# MotherboardRev1.net
KiCad netlist of a schematic drawn in EAGLE
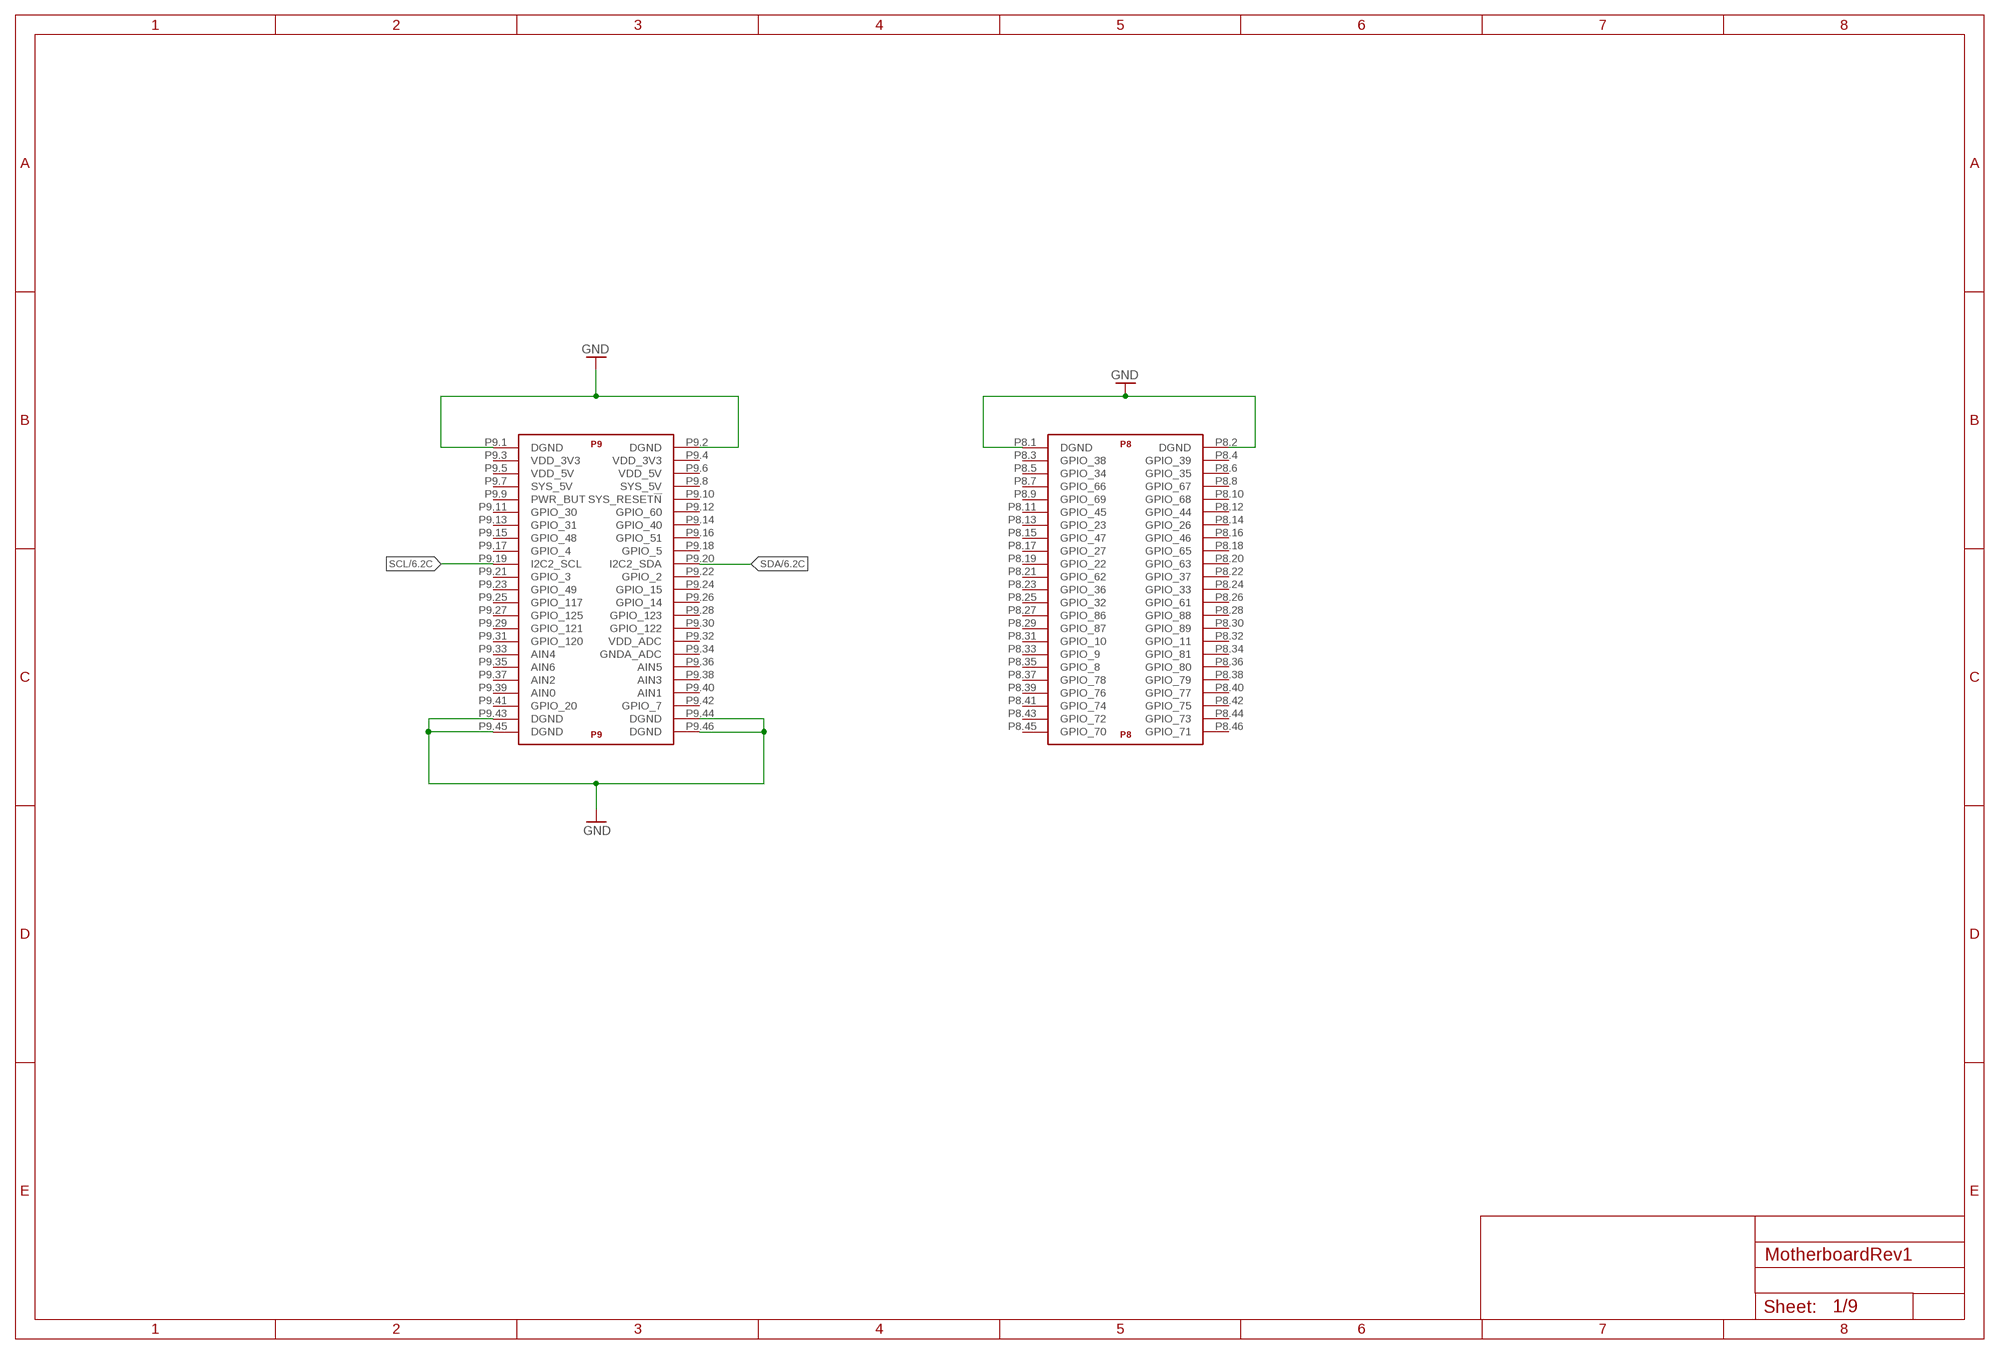
[diagram p0: schematic, sheet 1]
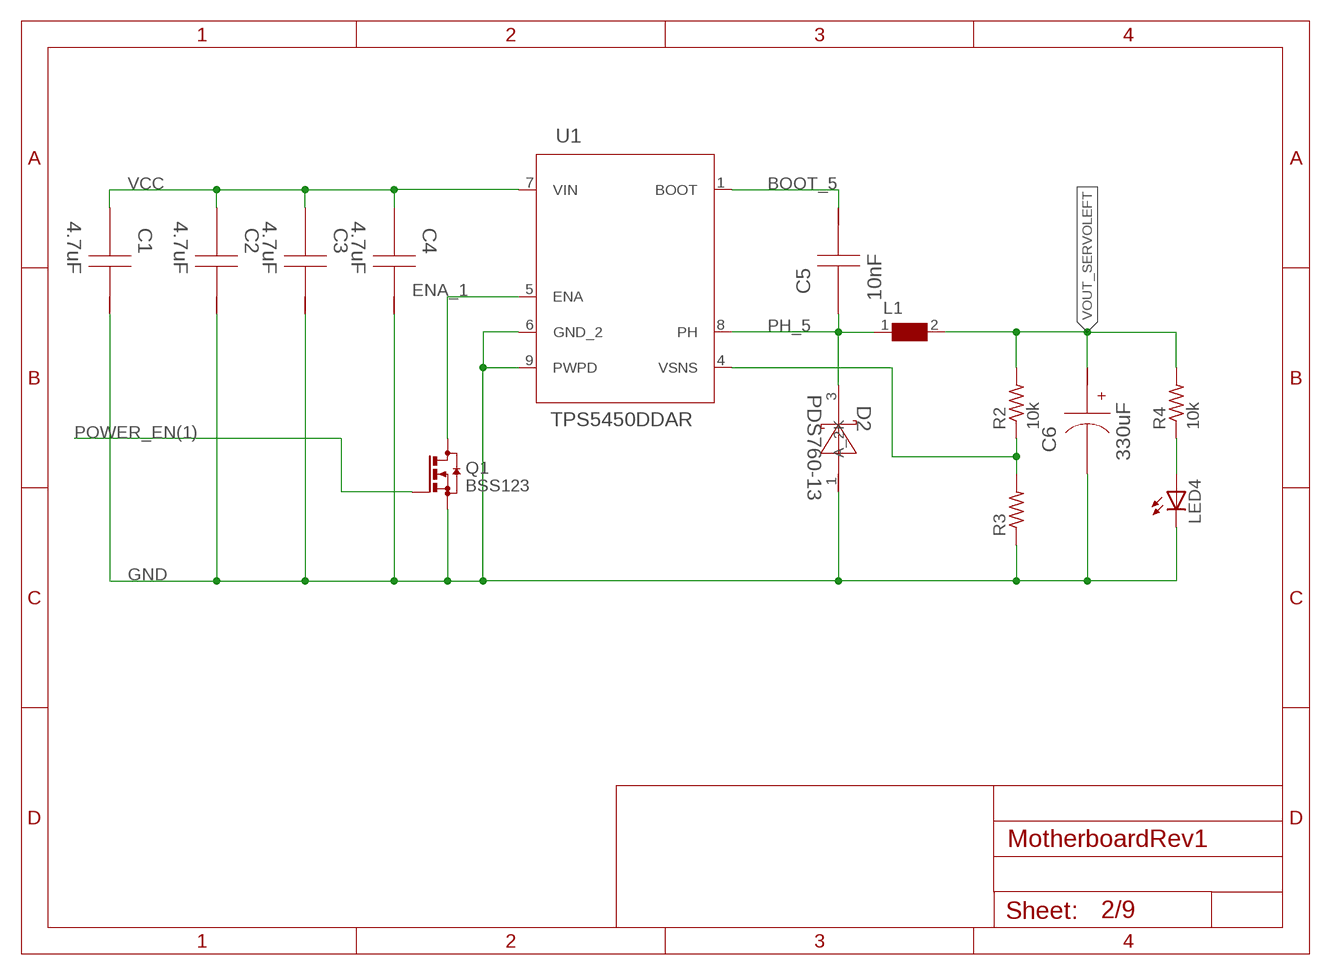
[diagram p1: schematic, sheet 2]
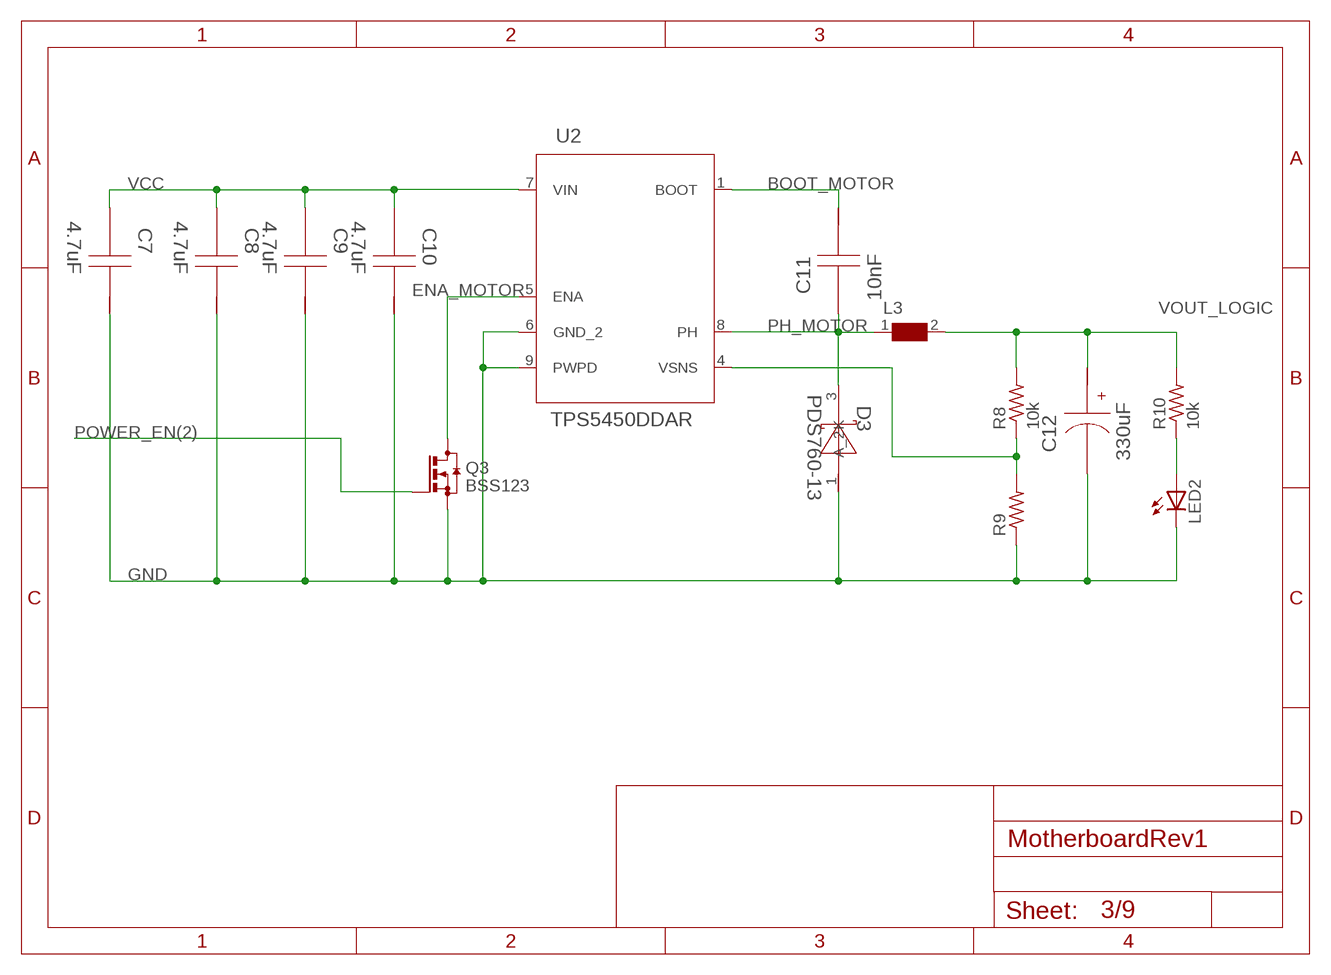
[diagram p2: schematic, sheet 3]
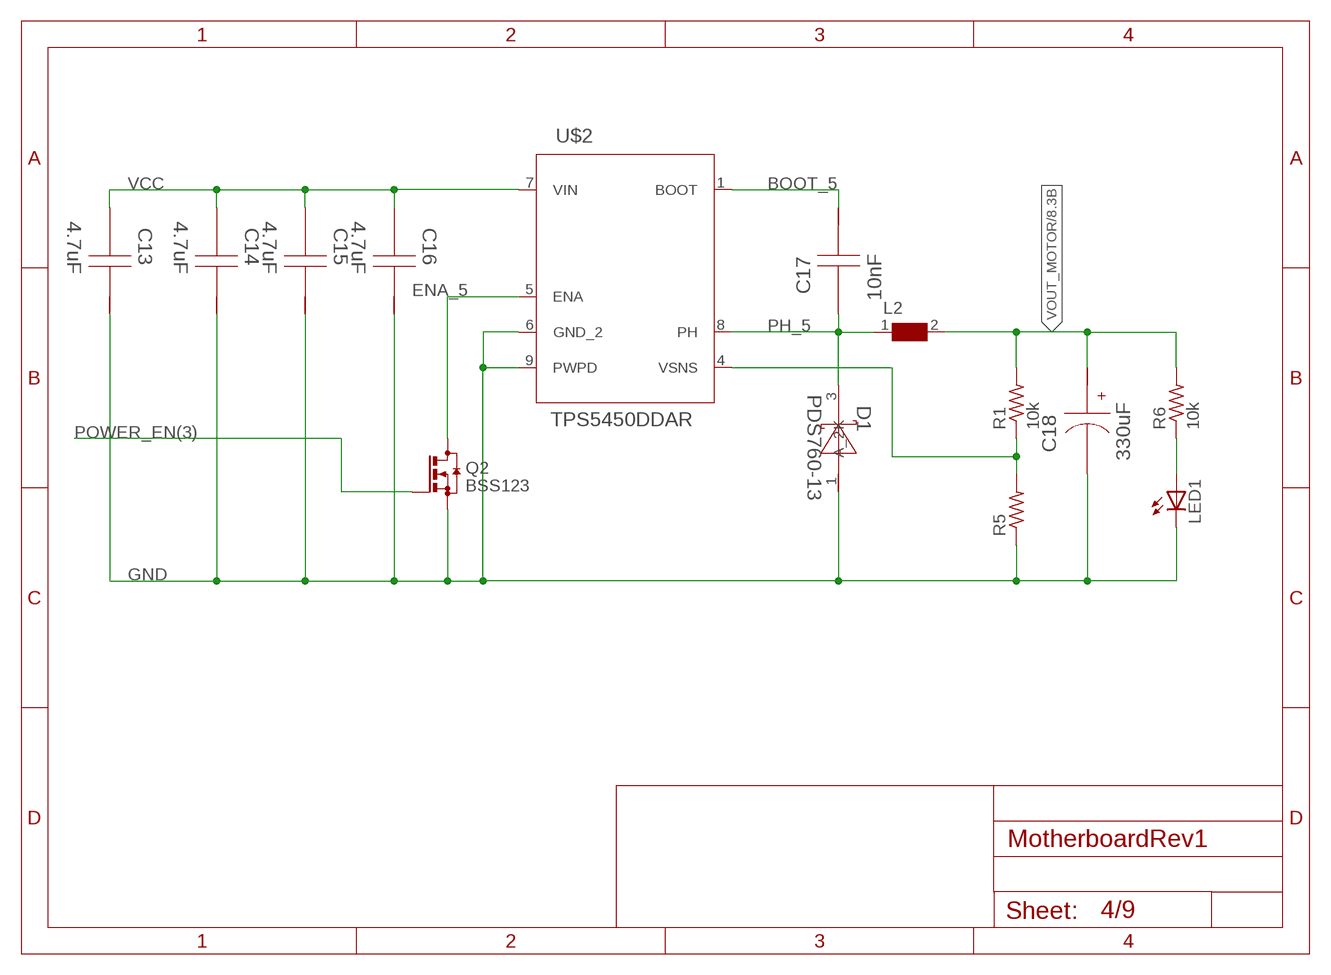
[diagram p3: schematic, sheet 4]
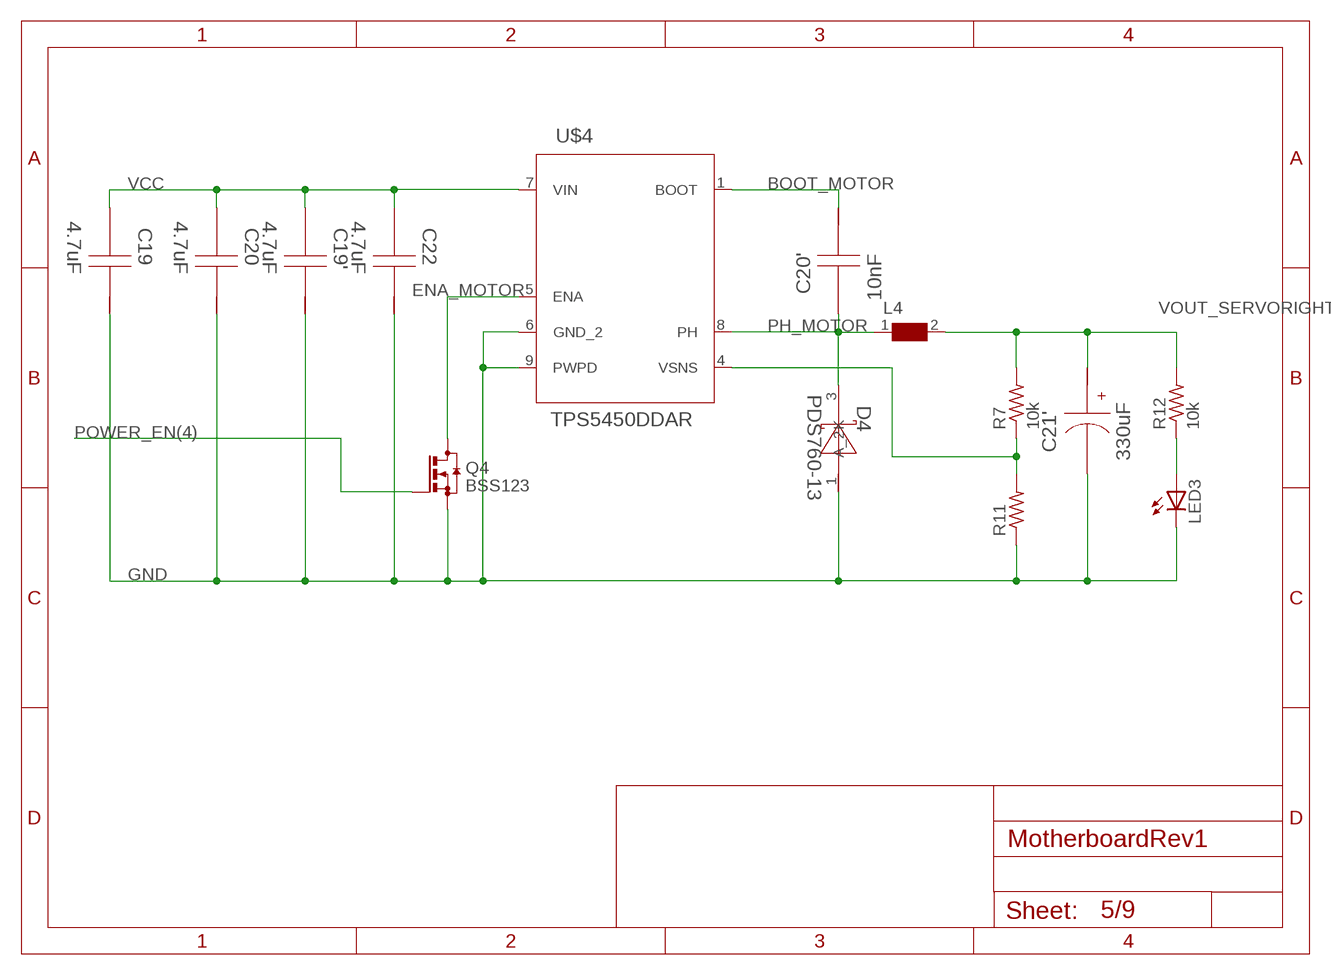
[diagram p4: schematic, sheet 5]
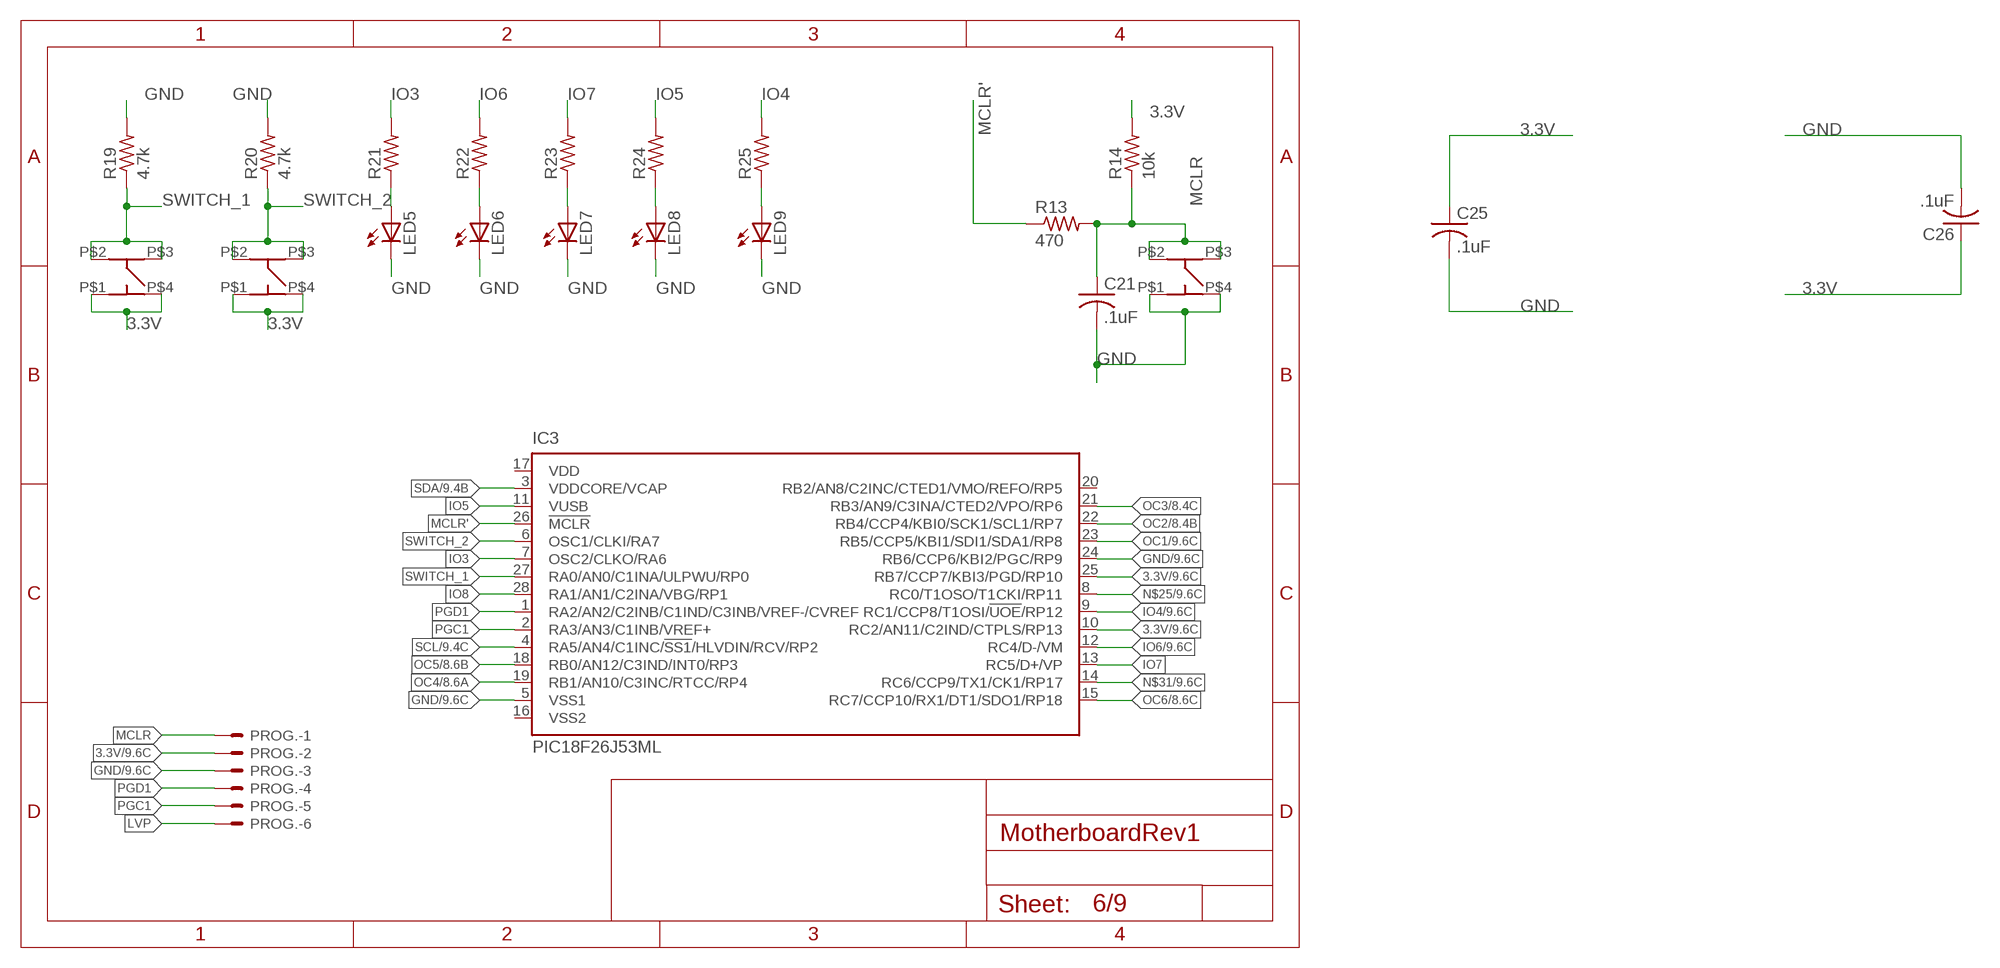
[diagram p5: schematic, sheet 6]
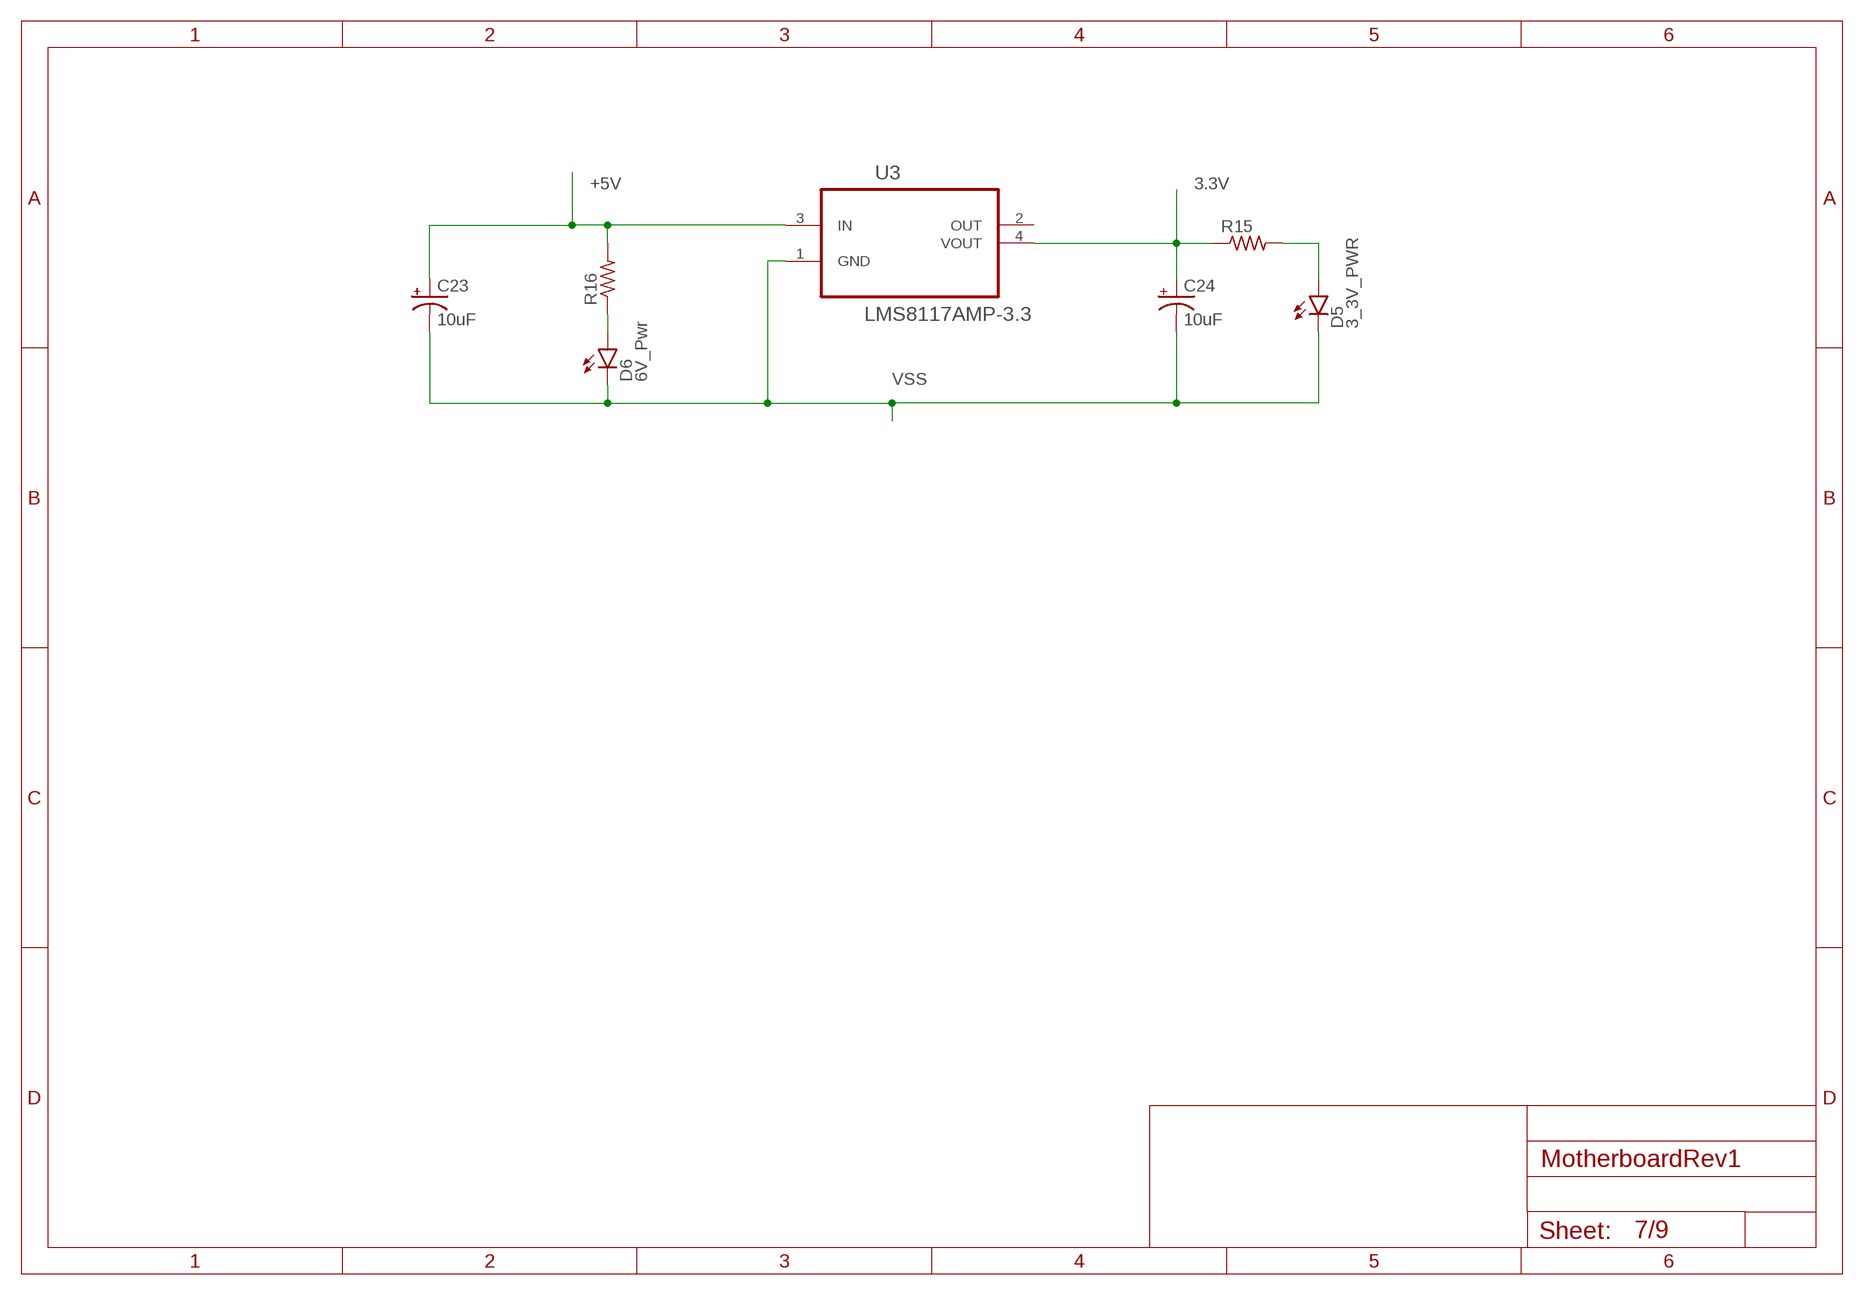
[diagram p6: schematic, sheet 7]
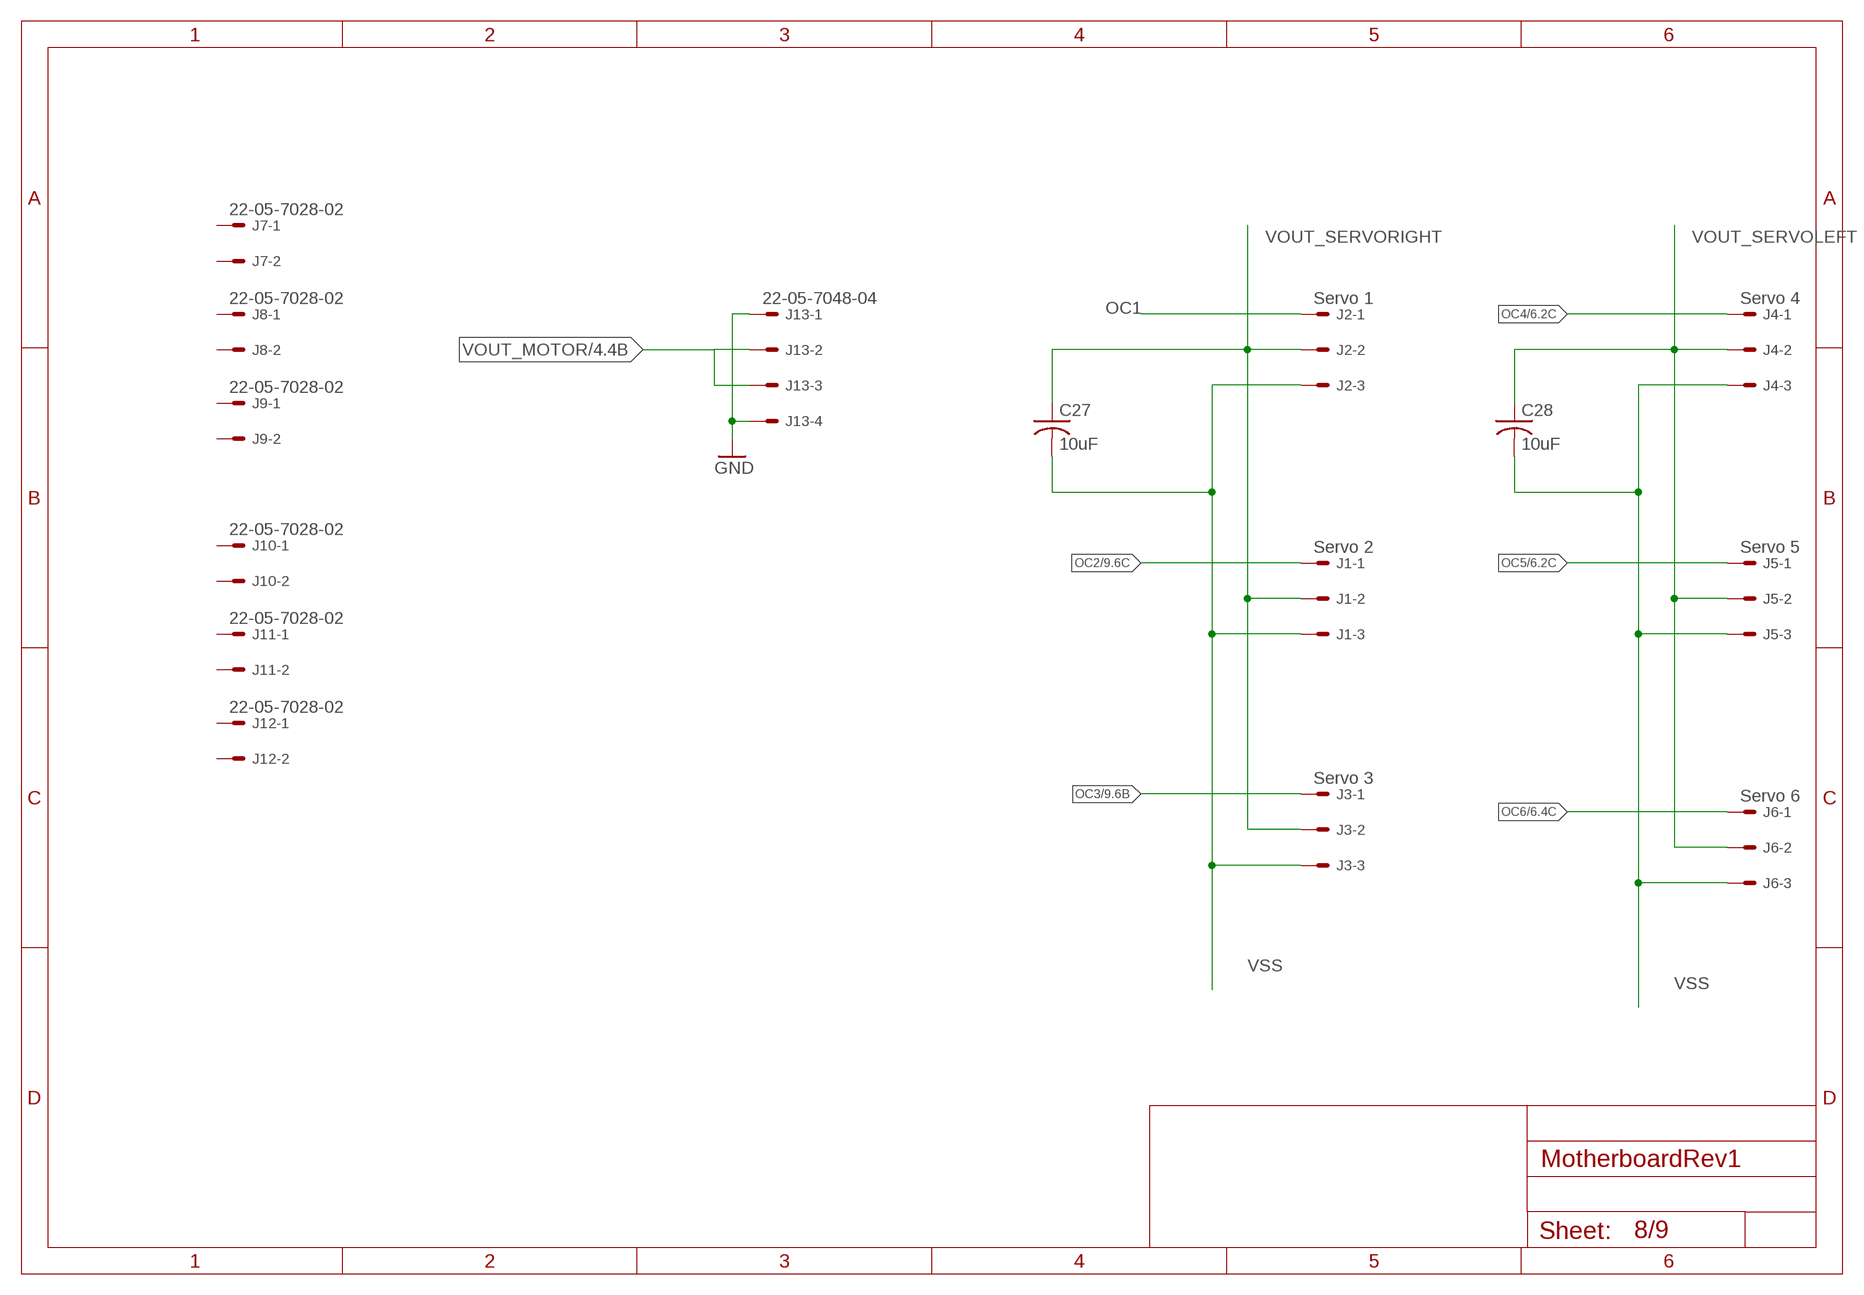
[diagram p7: schematic, sheet 8]
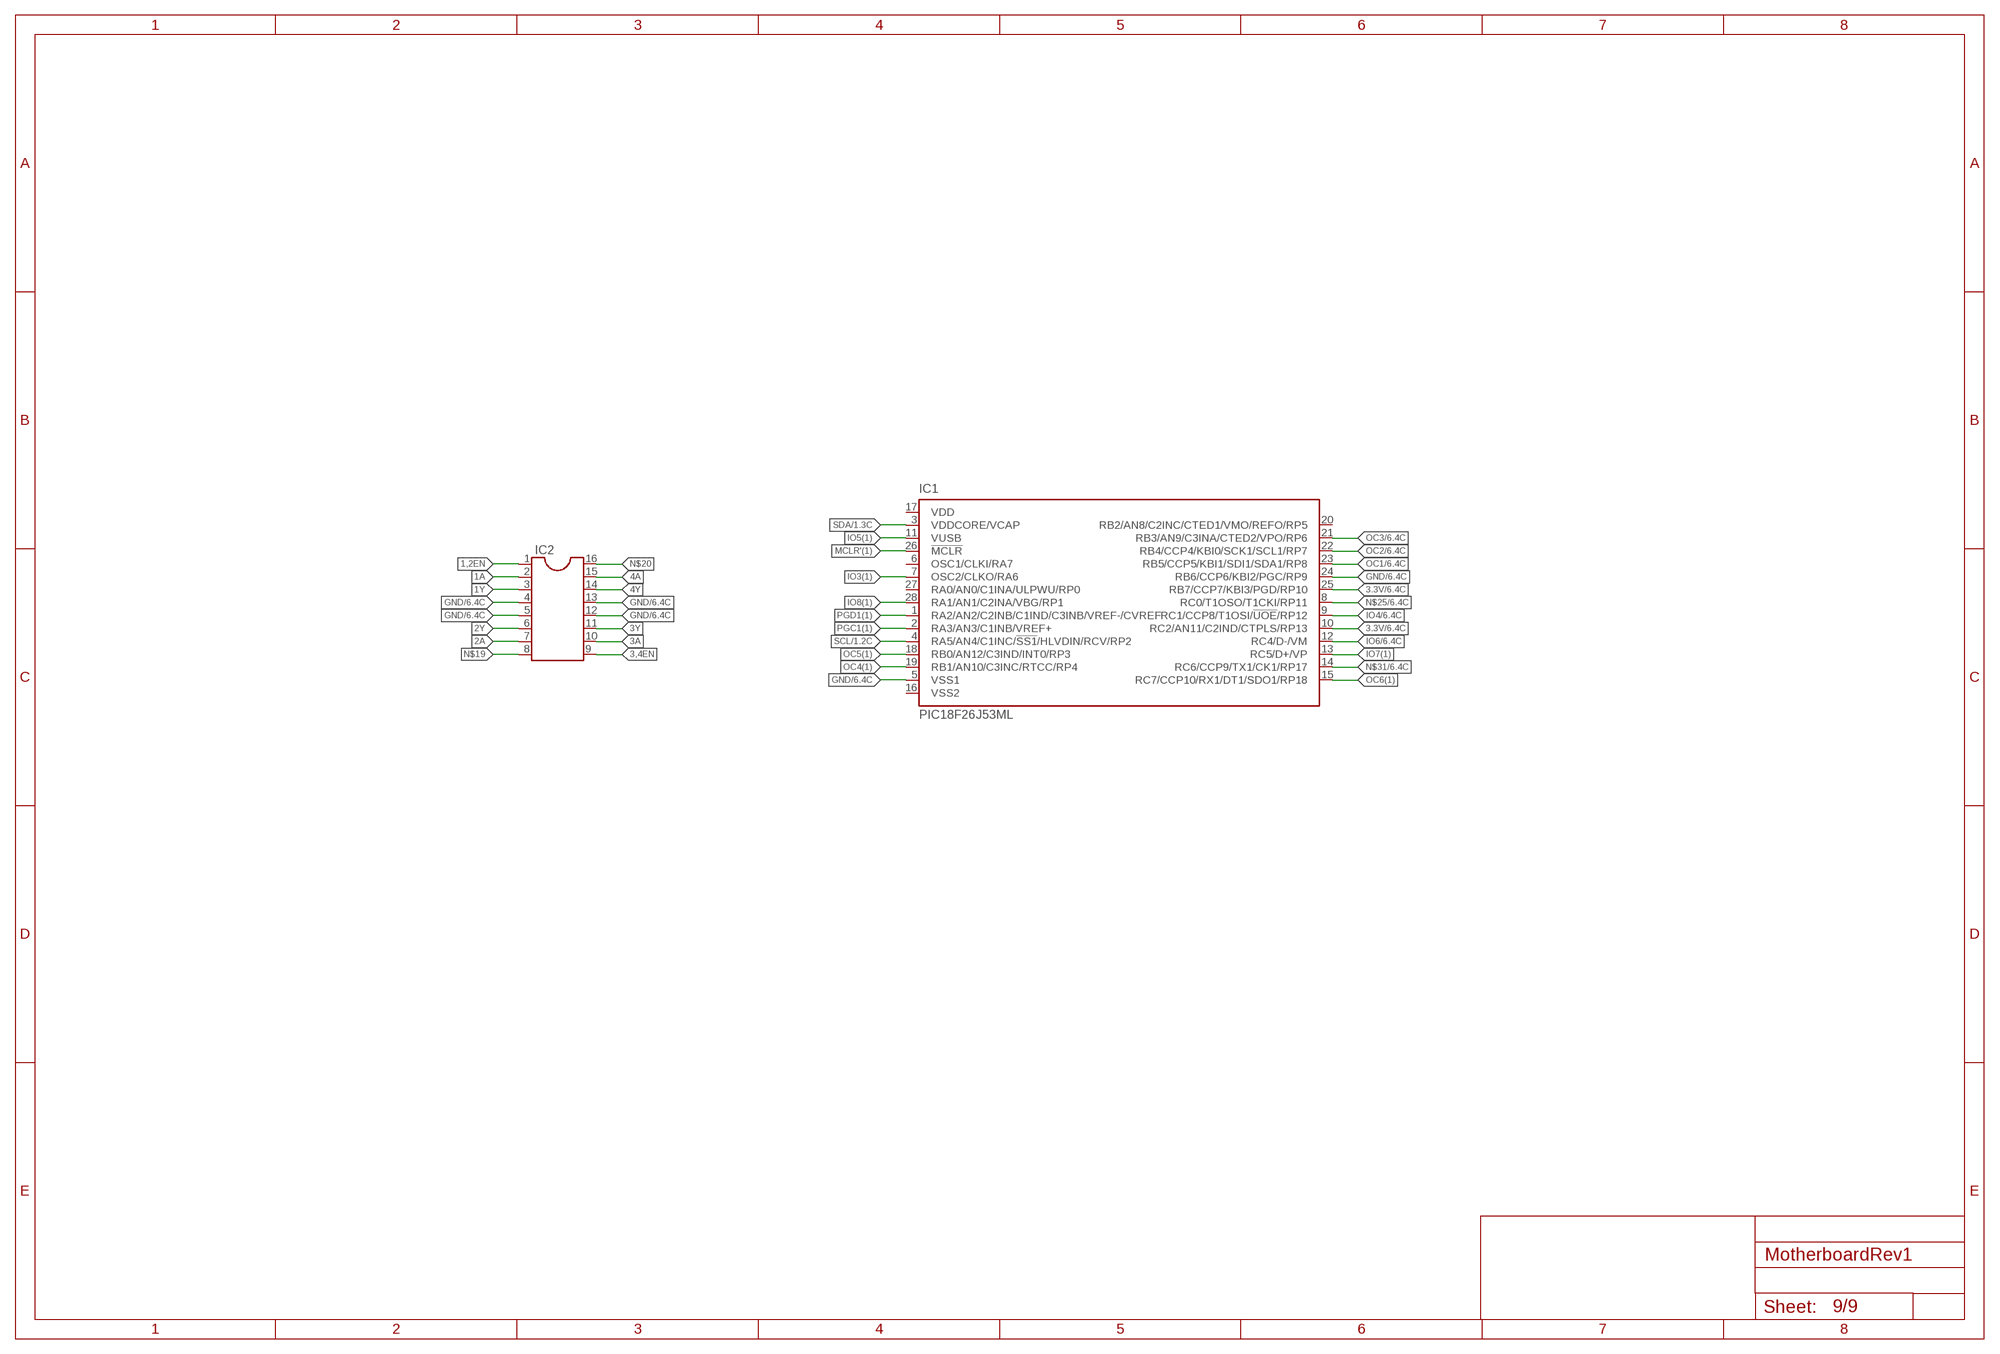
[diagram p8: schematic, sheet 9]

(export (version "E")
  (design (tool "Eeschema 10.0.6"))
  (components
    (comp (ref "C19")
      (value "4.7uF")
      (footprint "eagle-import:1206")
      (fields (field (name "MANUFACTURER_PART_NUMBER") "GRM31CR71H475KA12L"))
      (libsource (lib "eagle-import") (part "GRM31CR71H475KA12L"))
    )
    (comp (ref "C19'")
      (value "4.7uF")
      (footprint "eagle-import:1206")
      (fields (field (name "MANUFACTURER_PART_NUMBER") "GRM31CR71H475KA12L"))
      (libsource (lib "eagle-import") (part "GRM31CR71H475KA12L"))
    )
    (comp (ref "C20")
      (value "4.7uF")
      (footprint "eagle-import:1206")
      (fields (field (name "MANUFACTURER_PART_NUMBER") "GRM31CR71H475KA12L"))
      (libsource (lib "eagle-import") (part "GRM31CR71H475KA12L"))
    )
    (comp (ref "C20'")
      (value "10nF")
      (footprint "eagle-import:0805")
      (fields (field (name "MANUFACTURER_PART_NUMBER") "C0805C103K5RACTU"))
      (libsource (lib "eagle-import") (part "C0805C103K5RACTU"))
    )
    (comp (ref "C21'")
      (value "330uF")
      (footprint "eagle-import:SM_RADIAL_10AMM")
      (fields (field (name "MANUFACTURER_PART_NUMBER") "10SVP330MX"))
      (libsource (lib "eagle-import") (part "10SVP330MX"))
    )
    (comp (ref "C22")
      (value "4.7uF")
      (footprint "eagle-import:1206")
      (fields (field (name "MANUFACTURER_PART_NUMBER") "GRM31CR71H475KA12L"))
      (libsource (lib "eagle-import") (part "GRM31CR71H475KA12L"))
    )
    (comp (ref "D4")
      (value "PDS760-13")
      (footprint "eagle-import:POWERDI5")
      (libsource (lib "eagle-import") (part "PDS760-13"))
    )
    (comp (ref "L4")
      (value "WE-HCC-7443331000_1090")
      (footprint "eagle-import:WE-HCC_1090")
      (fields (field (name "MPN") "7443331000"))
      (libsource (lib "eagle-import") (part "WE-HCC_1090-7443331000"))
    )
    (comp (ref "LED3")
      (value "LEDSML1206")
      (footprint "eagle-import:SML1206")
      (libsource (lib "eagle-import") (part "LEDSML1206"))
    )
    (comp (ref "Q4")
      (value "BSS123")
      (footprint "eagle-import:SOT23")
      (libsource (lib "eagle-import") (part "BSS123"))
    )
    (comp (ref "R7")
      (value "10k")
      (footprint "eagle-import:R1206")
      (libsource (lib "eagle-import") (part "R-US_R1206"))
    )
    (comp (ref "R11")
      (value "R-US_R1206")
      (footprint "eagle-import:R1206")
      (libsource (lib "eagle-import") (part "R-US_R1206"))
    )
    (comp (ref "R12")
      (value "10k")
      (footprint "eagle-import:R1206")
      (libsource (lib "eagle-import") (part "R-US_R1206"))
    )
    (comp (ref "U$4")
      (value "TPS5450DDAR")
      (footprint "eagle-import:R-PDSO-G8")
      (fields (field (name "MANUFACTURER_PART_NUMBER") "TPS5450DDA"))
      (libsource (lib "eagle-import") (part "TPS5450DDAR"))
    )
    (comp (ref "C7")
      (value "4.7uF")
      (footprint "eagle-import:1206")
      (fields (field (name "MANUFACTURER_PART_NUMBER") "GRM31CR71H475KA12L"))
      (libsource (lib "eagle-import") (part "GRM31CR71H475KA12L"))
    )
    (comp (ref "C8")
      (value "4.7uF")
      (footprint "eagle-import:1206")
      (fields (field (name "MANUFACTURER_PART_NUMBER") "GRM31CR71H475KA12L"))
      (libsource (lib "eagle-import") (part "GRM31CR71H475KA12L"))
    )
    (comp (ref "C9")
      (value "4.7uF")
      (footprint "eagle-import:1206")
      (fields (field (name "MANUFACTURER_PART_NUMBER") "GRM31CR71H475KA12L"))
      (libsource (lib "eagle-import") (part "GRM31CR71H475KA12L"))
    )
    (comp (ref "C10")
      (value "4.7uF")
      (footprint "eagle-import:1206")
      (fields (field (name "MANUFACTURER_PART_NUMBER") "GRM31CR71H475KA12L"))
      (libsource (lib "eagle-import") (part "GRM31CR71H475KA12L"))
    )
    (comp (ref "C11")
      (value "10nF")
      (footprint "eagle-import:0805")
      (fields (field (name "MANUFACTURER_PART_NUMBER") "C0805C103K5RACTU"))
      (libsource (lib "eagle-import") (part "C0805C103K5RACTU"))
    )
    (comp (ref "C12")
      (value "330uF")
      (footprint "eagle-import:SM_RADIAL_10AMM")
      (fields (field (name "MANUFACTURER_PART_NUMBER") "10SVP330MX"))
      (libsource (lib "eagle-import") (part "10SVP330MX"))
    )
    (comp (ref "D3")
      (value "PDS760-13")
      (footprint "eagle-import:POWERDI5")
      (libsource (lib "eagle-import") (part "PDS760-13"))
    )
    (comp (ref "L3")
      (value "WE-HCC-7443331000_1090")
      (footprint "eagle-import:WE-HCC_1090")
      (fields (field (name "MPN") "7443331000"))
      (libsource (lib "eagle-import") (part "WE-HCC_1090-7443331000"))
    )
    (comp (ref "LED2")
      (value "LEDSML1206")
      (footprint "eagle-import:SML1206")
      (libsource (lib "eagle-import") (part "LEDSML1206"))
    )
    (comp (ref "Q3")
      (value "BSS123")
      (footprint "eagle-import:SOT23")
      (libsource (lib "eagle-import") (part "BSS123"))
    )
    (comp (ref "R8")
      (value "10k")
      (footprint "eagle-import:R1206")
      (libsource (lib "eagle-import") (part "R-US_R1206"))
    )
    (comp (ref "R9")
      (value "R-US_R1206")
      (footprint "eagle-import:R1206")
      (libsource (lib "eagle-import") (part "R-US_R1206"))
    )
    (comp (ref "R10")
      (value "10k")
      (footprint "eagle-import:R1206")
      (libsource (lib "eagle-import") (part "R-US_R1206"))
    )
    (comp (ref "U2")
      (value "TPS5450DDAR")
      (footprint "eagle-import:R-PDSO-G8")
      (fields (field (name "MANUFACTURER_PART_NUMBER") "TPS5450DDA"))
      (libsource (lib "eagle-import") (part "TPS5450DDAR"))
    )
    (comp (ref "U$1")
      (value "BEAGLE_BONE_BLACK_CAPE")
      (footprint "eagle-import:BEAGLE_BONE_BLACK_CAPE")
      (libsource (lib "eagle-import") (part "BEAGLE_BONE_BLACK_CAPE"))
    )
    (comp (ref "C1")
      (value "4.7uF")
      (footprint "eagle-import:1206")
      (fields (field (name "MANUFACTURER_PART_NUMBER") "GRM31CR71H475KA12L"))
      (libsource (lib "eagle-import") (part "GRM31CR71H475KA12L"))
    )
    (comp (ref "C2")
      (value "4.7uF")
      (footprint "eagle-import:1206")
      (fields (field (name "MANUFACTURER_PART_NUMBER") "GRM31CR71H475KA12L"))
      (libsource (lib "eagle-import") (part "GRM31CR71H475KA12L"))
    )
    (comp (ref "C3")
      (value "4.7uF")
      (footprint "eagle-import:1206")
      (fields (field (name "MANUFACTURER_PART_NUMBER") "GRM31CR71H475KA12L"))
      (libsource (lib "eagle-import") (part "GRM31CR71H475KA12L"))
    )
    (comp (ref "C4")
      (value "4.7uF")
      (footprint "eagle-import:1206")
      (fields (field (name "MANUFACTURER_PART_NUMBER") "GRM31CR71H475KA12L"))
      (libsource (lib "eagle-import") (part "GRM31CR71H475KA12L"))
    )
    (comp (ref "C5")
      (value "10nF")
      (footprint "eagle-import:0805")
      (fields (field (name "MANUFACTURER_PART_NUMBER") "C0805C103K5RACTU"))
      (libsource (lib "eagle-import") (part "C0805C103K5RACTU"))
    )
    (comp (ref "C6")
      (value "330uF")
      (footprint "eagle-import:SM_RADIAL_10AMM")
      (fields (field (name "MANUFACTURER_PART_NUMBER") "10SVP330MX"))
      (libsource (lib "eagle-import") (part "10SVP330MX"))
    )
    (comp (ref "D2")
      (value "PDS760-13")
      (footprint "eagle-import:POWERDI5")
      (libsource (lib "eagle-import") (part "PDS760-13"))
    )
    (comp (ref "L1")
      (value "WE-HCC-7443331000_1090")
      (footprint "eagle-import:WE-HCC_1090")
      (fields (field (name "MPN") "7443331000"))
      (libsource (lib "eagle-import") (part "WE-HCC_1090-7443331000"))
    )
    (comp (ref "LED4")
      (value "LEDSML1206")
      (footprint "eagle-import:SML1206")
      (libsource (lib "eagle-import") (part "LEDSML1206"))
    )
    (comp (ref "Q1")
      (value "BSS123")
      (footprint "eagle-import:SOT23")
      (libsource (lib "eagle-import") (part "BSS123"))
    )
    (comp (ref "R2")
      (value "10k")
      (footprint "eagle-import:R1206")
      (libsource (lib "eagle-import") (part "R-US_R1206"))
    )
    (comp (ref "R3")
      (value "R-US_R1206")
      (footprint "eagle-import:R1206")
      (libsource (lib "eagle-import") (part "R-US_R1206"))
    )
    (comp (ref "R4")
      (value "10k")
      (footprint "eagle-import:R1206")
      (libsource (lib "eagle-import") (part "R-US_R1206"))
    )
    (comp (ref "U1")
      (value "TPS5450DDAR")
      (footprint "eagle-import:R-PDSO-G8")
      (fields (field (name "MANUFACTURER_PART_NUMBER") "TPS5450DDA"))
      (libsource (lib "eagle-import") (part "TPS5450DDAR"))
    )
    (comp (ref "IC1")
      (value "PIC18F26J53ML")
      (footprint "eagle-import:QFN28-ML_6X6MM")
      (fields (field (name "MPN") "PIC18F26J53-I/ML"))
      (libsource (lib "eagle-import") (part "PIC18F2J53ML6"))
    )
    (comp (ref "IC2")
      (value "DIL16")
      (footprint "eagle-import:DIL16")
      (libsource (lib "eagle-import") (part "DIL16"))
    )
    (comp (ref "C23")
      (value "10uF")
      (footprint "eagle-import:EIA3216")
      (libsource (lib "eagle-import") (part "10UF-16V-10%(TANT)"))
    )
    (comp (ref "C24")
      (value "10uF")
      (footprint "eagle-import:EIA3216")
      (libsource (lib "eagle-import") (part "10UF-16V-10%(TANT)"))
    )
    (comp (ref "D5")
      (value "3_3V_PWR")
      (footprint "eagle-import:FKIT-LED-1206")
      (libsource (lib "eagle-import") (part "LED-FKIT-1206"))
    )
    (comp (ref "D6")
      (value "6V_Pwr")
      (footprint "eagle-import:FKIT-LED-1206")
      (libsource (lib "eagle-import") (part "LED-FKIT-1206"))
    )
    (comp (ref "R15")
      (value "R-US_R0805W")
      (footprint "eagle-import:R0805W")
      (libsource (lib "eagle-import") (part "R-US_R0805W"))
    )
    (comp (ref "R16")
      (value "R-US_R0805W")
      (footprint "eagle-import:R0805W")
      (libsource (lib "eagle-import") (part "R-US_R0805W"))
    )
    (comp (ref "U3")
      (value "LMS8117AMP-3.3")
      (footprint "eagle-import:SOT230P696X180-4N")
      (libsource (lib "eagle-import") (part "LMS8117AMP-3.3"))
    )
    (comp (ref "C13")
      (value "4.7uF")
      (footprint "eagle-import:1206")
      (fields (field (name "MANUFACTURER_PART_NUMBER") "GRM31CR71H475KA12L"))
      (libsource (lib "eagle-import") (part "GRM31CR71H475KA12L"))
    )
    (comp (ref "C14")
      (value "4.7uF")
      (footprint "eagle-import:1206")
      (fields (field (name "MANUFACTURER_PART_NUMBER") "GRM31CR71H475KA12L"))
      (libsource (lib "eagle-import") (part "GRM31CR71H475KA12L"))
    )
    (comp (ref "C15")
      (value "4.7uF")
      (footprint "eagle-import:1206")
      (fields (field (name "MANUFACTURER_PART_NUMBER") "GRM31CR71H475KA12L"))
      (libsource (lib "eagle-import") (part "GRM31CR71H475KA12L"))
    )
    (comp (ref "C16")
      (value "4.7uF")
      (footprint "eagle-import:1206")
      (fields (field (name "MANUFACTURER_PART_NUMBER") "GRM31CR71H475KA12L"))
      (libsource (lib "eagle-import") (part "GRM31CR71H475KA12L"))
    )
    (comp (ref "C17")
      (value "10nF")
      (footprint "eagle-import:0805")
      (fields (field (name "MANUFACTURER_PART_NUMBER") "C0805C103K5RACTU"))
      (libsource (lib "eagle-import") (part "C0805C103K5RACTU"))
    )
    (comp (ref "C18")
      (value "330uF")
      (footprint "eagle-import:SM_RADIAL_10AMM")
      (fields (field (name "MANUFACTURER_PART_NUMBER") "10SVP330MX"))
      (libsource (lib "eagle-import") (part "10SVP330MX"))
    )
    (comp (ref "D1")
      (value "PDS760-13")
      (footprint "eagle-import:POWERDI5")
      (libsource (lib "eagle-import") (part "PDS760-13"))
    )
    (comp (ref "L2")
      (value "WE-HCC-7443331000_1090")
      (footprint "eagle-import:WE-HCC_1090")
      (fields (field (name "MPN") "7443331000"))
      (libsource (lib "eagle-import") (part "WE-HCC_1090-7443331000"))
    )
    (comp (ref "LED1")
      (value "LEDSML1206")
      (footprint "eagle-import:SML1206")
      (libsource (lib "eagle-import") (part "LEDSML1206"))
    )
    (comp (ref "Q2")
      (value "BSS123")
      (footprint "eagle-import:SOT23")
      (libsource (lib "eagle-import") (part "BSS123"))
    )
    (comp (ref "R1")
      (value "10k")
      (footprint "eagle-import:R1206")
      (libsource (lib "eagle-import") (part "R-US_R1206"))
    )
    (comp (ref "R5")
      (value "R-US_R1206")
      (footprint "eagle-import:R1206")
      (libsource (lib "eagle-import") (part "R-US_R1206"))
    )
    (comp (ref "R6")
      (value "10k")
      (footprint "eagle-import:R1206")
      (libsource (lib "eagle-import") (part "R-US_R1206"))
    )
    (comp (ref "U$2")
      (value "TPS5450DDAR")
      (footprint "eagle-import:R-PDSO-G8")
      (fields (field (name "MANUFACTURER_PART_NUMBER") "TPS5450DDA"))
      (libsource (lib "eagle-import") (part "TPS5450DDAR"))
    )
    (comp (ref "C27")
      (value "10uF")
      (footprint "eagle-import:C0805")
      (libsource (lib "eagle-import") (part "C-USC0805"))
    )
    (comp (ref "C28")
      (value "10uF")
      (footprint "eagle-import:C0805")
      (libsource (lib "eagle-import") (part "C-USC0805"))
    )
    (comp (ref "J1")
      (value "Servo 2")
      (footprint "eagle-import:7395-03")
      (libsource (lib "eagle-import") (part "22-?-0305-7038"))
    )
    (comp (ref "J2")
      (value "Servo 1")
      (footprint "eagle-import:7395-03")
      (libsource (lib "eagle-import") (part "22-?-0305-7038"))
    )
    (comp (ref "J3")
      (value "Servo 3")
      (footprint "eagle-import:7395-03")
      (libsource (lib "eagle-import") (part "22-?-0305-7038"))
    )
    (comp (ref "J4")
      (value "Servo 4")
      (footprint "eagle-import:7395-03")
      (libsource (lib "eagle-import") (part "22-?-0305-7038"))
    )
    (comp (ref "J5")
      (value "Servo 5")
      (footprint "eagle-import:7395-03")
      (libsource (lib "eagle-import") (part "22-?-0305-7038"))
    )
    (comp (ref "J6")
      (value "Servo 6")
      (footprint "eagle-import:7395-03")
      (libsource (lib "eagle-import") (part "22-?-0305-7038"))
    )
    (comp (ref "J7")
      (value "22-05-7028-02")
      (footprint "eagle-import:7395-02")
      (libsource (lib "eagle-import") (part "22-?-0205-7028"))
    )
    (comp (ref "J8")
      (value "22-05-7028-02")
      (footprint "eagle-import:7395-02")
      (libsource (lib "eagle-import") (part "22-?-0205-7028"))
    )
    (comp (ref "J9")
      (value "22-05-7028-02")
      (footprint "eagle-import:7395-02")
      (libsource (lib "eagle-import") (part "22-?-0205-7028"))
    )
    (comp (ref "J10")
      (value "22-05-7028-02")
      (footprint "eagle-import:7395-02")
      (libsource (lib "eagle-import") (part "22-?-0205-7028"))
    )
    (comp (ref "J11")
      (value "22-05-7028-02")
      (footprint "eagle-import:7395-02")
      (libsource (lib "eagle-import") (part "22-?-0205-7028"))
    )
    (comp (ref "J12")
      (value "22-05-7028-02")
      (footprint "eagle-import:7395-02")
      (libsource (lib "eagle-import") (part "22-?-0205-7028"))
    )
    (comp (ref "J13")
      (value "22-05-7048-04")
      (footprint "eagle-import:7395-04")
      (libsource (lib "eagle-import") (part "22-?-0405-7048"))
    )
    (comp (ref "C21")
      (value ".1uF")
      (footprint "eagle-import:C0805")
      (libsource (lib "eagle-import") (part "C-USC0805"))
    )
    (comp (ref "C25")
      (value ".1uF")
      (footprint "eagle-import:C0805")
      (libsource (lib "eagle-import") (part "C-USC0805"))
    )
    (comp (ref "C26")
      (value ".1uF")
      (footprint "eagle-import:C0805")
      (libsource (lib "eagle-import") (part "C-USC0805"))
    )
    (comp (ref "IC3")
      (value "PIC18F26J53ML")
      (footprint "eagle-import:QFN28-ML_6X6MM")
      (fields (field (name "MPN") "PIC18F26J53-I/ML"))
      (libsource (lib "eagle-import") (part "PIC18F2J53ML6"))
    )
    (comp (ref "LED5")
      (value "LED_LEDCHIPLED_1206")
      (footprint "eagle-import:LED_CHIPLED_1206")
      (libsource (lib "eagle-import") (part "LED_LEDCHIPLED_1206"))
    )
    (comp (ref "LED6")
      (value "LED_LEDCHIPLED_1206")
      (footprint "eagle-import:LED_CHIPLED_1206")
      (libsource (lib "eagle-import") (part "LED_LEDCHIPLED_1206"))
    )
    (comp (ref "LED7")
      (value "LED_LEDCHIPLED_1206")
      (footprint "eagle-import:LED_CHIPLED_1206")
      (libsource (lib "eagle-import") (part "LED_LEDCHIPLED_1206"))
    )
    (comp (ref "LED8")
      (value "LED_LEDCHIPLED_1206")
      (footprint "eagle-import:LED_CHIPLED_1206")
      (libsource (lib "eagle-import") (part "LED_LEDCHIPLED_1206"))
    )
    (comp (ref "LED9")
      (value "LED_LEDCHIPLED_1206")
      (footprint "eagle-import:LED_CHIPLED_1206")
      (libsource (lib "eagle-import") (part "LED_LEDCHIPLED_1206"))
    )
    (comp (ref "PROG.")
      (value "22-23-2061")
      (footprint "eagle-import:22-23-2061")
      (fields (field (name "MF") "MOLEX"))
      (libsource (lib "eagle-import") (part "22-23-2061"))
    )
    (comp (ref "R13")
      (value "470")
      (footprint "eagle-import:R0805")
      (libsource (lib "eagle-import") (part "R-US_R0805"))
    )
    (comp (ref "R14")
      (value "10k")
      (footprint "eagle-import:R0805")
      (libsource (lib "eagle-import") (part "R-US_R0805"))
    )
    (comp (ref "R19")
      (value "4.7k")
      (footprint "eagle-import:R0805")
      (libsource (lib "eagle-import") (part "R-US_R0805"))
    )
    (comp (ref "R20")
      (value "4.7k")
      (footprint "eagle-import:R0805")
      (libsource (lib "eagle-import") (part "R-US_R0805"))
    )
    (comp (ref "R21")
      (value "R-US_M0805")
      (footprint "eagle-import:M0805")
      (libsource (lib "eagle-import") (part "R-US_M0805"))
    )
    (comp (ref "R22")
      (value "R-US_M0805")
      (footprint "eagle-import:M0805")
      (libsource (lib "eagle-import") (part "R-US_M0805"))
    )
    (comp (ref "R23")
      (value "R-US_M0805")
      (footprint "eagle-import:M0805")
      (libsource (lib "eagle-import") (part "R-US_M0805"))
    )
    (comp (ref "R24")
      (value "R-US_M0805")
      (footprint "eagle-import:M0805")
      (libsource (lib "eagle-import") (part "R-US_M0805"))
    )
    (comp (ref "R25")
      (value "R-US_M0805")
      (footprint "eagle-import:M0805")
      (libsource (lib "eagle-import") (part "R-US_M0805"))
    )
    (comp (ref "U$5")
      (value "Switch3")
      (footprint "eagle-import:MC32882_FINAL")
      (libsource (lib "eagle-import") (part "MC32882_SW"))
    )
    (comp (ref "U$6")
      (value "Switch1")
      (footprint "eagle-import:MC32882_FINAL")
      (libsource (lib "eagle-import") (part "MC32882_SW"))
    )
    (comp (ref "U$7")
      (value "Switch2")
      (footprint "eagle-import:MC32882_FINAL")
      (libsource (lib "eagle-import") (part "MC32882_SW"))
    )
  )
  (nets
    (net (code "1") (name "+5V") (class "Default")
      (node (ref "C23") (pin "A") (pinfunction "+_A") (pintype "passive"))
      (node (ref "R16") (pin "2") (pinfunction "2_2") (pintype "passive"))
      (node (ref "U3") (pin "3") (pinfunction "IN_3") (pintype "power_in"))
    )
    (net (code "2") (name "1,2EN") (class "Default")
      (node (ref "IC2") (pin "1") (pinfunction "1_1") (pintype "passive"))
    )
    (net (code "3") (name "1A") (class "Default")
      (node (ref "IC2") (pin "2") (pinfunction "2_2") (pintype "passive"))
    )
    (net (code "4") (name "1Y") (class "Default")
      (node (ref "IC2") (pin "3") (pinfunction "3_3") (pintype "passive"))
    )
    (net (code "5") (name "2A") (class "Default")
      (node (ref "IC2") (pin "7") (pinfunction "7_7") (pintype "passive"))
    )
    (net (code "6") (name "2Y") (class "Default")
      (node (ref "IC2") (pin "6") (pinfunction "6_6") (pintype "passive"))
    )
    (net (code "7") (name "3,4EN") (class "Default")
      (node (ref "IC2") (pin "9") (pinfunction "9_9") (pintype "passive"))
    )
    (net (code "8") (name "3.3V") (class "Default")
      (node (ref "C24") (pin "A") (pinfunction "+_A") (pintype "passive"))
      (node (ref "C25") (pin "1") (pinfunction "1_1") (pintype "passive"))
      (node (ref "C26") (pin "1") (pinfunction "1_1") (pintype "passive"))
      (node (ref "IC1") (pin "10") (pinfunction "RC2/AN11/C2IND/CTPLS/RP13_10") (pintype "bidirectional"))
      (node (ref "IC1") (pin "25") (pinfunction "RB7/CCP7/KBI3/PGD/RP10_25") (pintype "bidirectional"))
      (node (ref "IC3") (pin "10") (pinfunction "RC2/AN11/C2IND/CTPLS/RP13_10") (pintype "bidirectional"))
      (node (ref "IC3") (pin "25") (pinfunction "RB7/CCP7/KBI3/PGD/RP10_25") (pintype "bidirectional"))
      (node (ref "PROG.") (pin "2") (pinfunction "S_2") (pintype "passive"))
      (node (ref "R14") (pin "2") (pinfunction "2_2") (pintype "passive"))
      (node (ref "R15") (pin "1") (pinfunction "1_1") (pintype "passive"))
      (node (ref "U$6") (pin "P$1") (pinfunction "P1_P$1") (pintype "bidirectional"))
      (node (ref "U$6") (pin "P$4") (pinfunction "P4_P$4") (pintype "bidirectional"))
      (node (ref "U$7") (pin "P$1") (pinfunction "P1_P$1") (pintype "bidirectional"))
      (node (ref "U$7") (pin "P$4") (pinfunction "P4_P$4") (pintype "bidirectional"))
      (node (ref "U3") (pin "4") (pinfunction "VOUT_4") (pintype "power_in"))
    )
    (net (code "9") (name "3A") (class "Default")
      (node (ref "IC2") (pin "10") (pinfunction "10_10") (pintype "passive"))
    )
    (net (code "10") (name "3Y") (class "Default")
      (node (ref "IC2") (pin "11") (pinfunction "11_11") (pintype "passive"))
    )
    (net (code "11") (name "4A") (class "Default")
      (node (ref "IC2") (pin "15") (pinfunction "15_15") (pintype "passive"))
    )
    (net (code "12") (name "4Y") (class "Default")
      (node (ref "IC2") (pin "14") (pinfunction "14_14") (pintype "passive"))
    )
    (net (code "13") (name "BOOT_5") (class "Default")
      (node (ref "C17") (pin "1") (pinfunction "1_1") (pintype "passive"))
      (node (ref "C5") (pin "1") (pinfunction "1_1") (pintype "passive"))
      (node (ref "U$2") (pin "1") (pinfunction "BOOT_1") (pintype "passive"))
      (node (ref "U1") (pin "1") (pinfunction "BOOT_1") (pintype "passive"))
    )
    (net (code "14") (name "BOOT_MOTOR") (class "Default")
      (node (ref "C11") (pin "1") (pinfunction "1_1") (pintype "passive"))
      (node (ref "C20'") (pin "1") (pinfunction "1_1") (pintype "passive"))
      (node (ref "U$4") (pin "1") (pinfunction "BOOT_1") (pintype "passive"))
      (node (ref "U2") (pin "1") (pinfunction "BOOT_1") (pintype "passive"))
    )
    (net (code "15") (name "ENA_1") (class "Default")
      (node (ref "Q1") (pin "3") (pinfunction "D_3") (pintype "passive"))
      (node (ref "U1") (pin "5") (pinfunction "ENA_5") (pintype "passive"))
    )
    (net (code "16") (name "ENA_5") (class "Default")
      (node (ref "Q2") (pin "3") (pinfunction "D_3") (pintype "passive"))
      (node (ref "U$2") (pin "5") (pinfunction "ENA_5") (pintype "passive"))
    )
    (net (code "17") (name "ENA_MOTOR") (class "Default")
      (node (ref "Q3") (pin "3") (pinfunction "D_3") (pintype "passive"))
      (node (ref "Q4") (pin "3") (pinfunction "D_3") (pintype "passive"))
      (node (ref "U$4") (pin "5") (pinfunction "ENA_5") (pintype "passive"))
      (node (ref "U2") (pin "5") (pinfunction "ENA_5") (pintype "passive"))
    )
    (net (code "18") (name "GND") (class "Default")
      (node (ref "C1") (pin "1") (pinfunction "1_1") (pintype "passive"))
      (node (ref "C10") (pin "1") (pinfunction "1_1") (pintype "passive"))
      (node (ref "C12") (pin "2") (pinfunction "-_2") (pintype "passive"))
      (node (ref "C13") (pin "1") (pinfunction "1_1") (pintype "passive"))
      (node (ref "C14") (pin "1") (pinfunction "1_1") (pintype "passive"))
      (node (ref "C15") (pin "1") (pinfunction "1_1") (pintype "passive"))
      (node (ref "C16") (pin "1") (pinfunction "1_1") (pintype "passive"))
      (node (ref "C18") (pin "2") (pinfunction "-_2") (pintype "passive"))
      (node (ref "C19") (pin "1") (pinfunction "1_1") (pintype "passive"))
      (node (ref "C19'") (pin "1") (pinfunction "1_1") (pintype "passive"))
      (node (ref "C2") (pin "1") (pinfunction "1_1") (pintype "passive"))
      (node (ref "C20") (pin "1") (pinfunction "1_1") (pintype "passive"))
      (node (ref "C21") (pin "2") (pinfunction "2_2") (pintype "passive"))
      (node (ref "C21'") (pin "2") (pinfunction "-_2") (pintype "passive"))
      (node (ref "C22") (pin "1") (pinfunction "1_1") (pintype "passive"))
      (node (ref "C25") (pin "2") (pinfunction "2_2") (pintype "passive"))
      (node (ref "C26") (pin "2") (pinfunction "2_2") (pintype "passive"))
      (node (ref "C3") (pin "1") (pinfunction "1_1") (pintype "passive"))
      (node (ref "C4") (pin "1") (pinfunction "1_1") (pintype "passive"))
      (node (ref "C6") (pin "2") (pinfunction "-_2") (pintype "passive"))
      (node (ref "C7") (pin "1") (pinfunction "1_1") (pintype "passive"))
      (node (ref "C8") (pin "1") (pinfunction "1_1") (pintype "passive"))
      (node (ref "C9") (pin "1") (pinfunction "1_1") (pintype "passive"))
      (node (ref "D1") (pin "1") (pinfunction "A_2_1") (pintype "passive"))
      (node (ref "D2") (pin "1") (pinfunction "A_2_1") (pintype "passive"))
      (node (ref "D3") (pin "1") (pinfunction "A_2_1") (pintype "passive"))
      (node (ref "D4") (pin "1") (pinfunction "A_2_1") (pintype "passive"))
      (node (ref "IC1") (pin "24") (pinfunction "RB6/CCP6/KBI2/PGC/RP9_24") (pintype "bidirectional"))
      (node (ref "IC1") (pin "5") (pinfunction "VSS1_5") (pintype "input"))
      (node (ref "IC2") (pin "12") (pinfunction "12_12") (pintype "passive"))
      (node (ref "IC2") (pin "13") (pinfunction "13_13") (pintype "passive"))
      (node (ref "IC2") (pin "4") (pinfunction "4_4") (pintype "passive"))
      (node (ref "IC2") (pin "5") (pinfunction "5_5") (pintype "passive"))
      (node (ref "IC3") (pin "24") (pinfunction "RB6/CCP6/KBI2/PGC/RP9_24") (pintype "bidirectional"))
      (node (ref "IC3") (pin "5") (pinfunction "VSS1_5") (pintype "input"))
      (node (ref "J13") (pin "1") (pinfunction "S_1") (pintype "passive"))
      (node (ref "J13") (pin "4") (pinfunction "S_4") (pintype "passive"))
      (node (ref "LED1") (pin "C") (pinfunction "C_C") (pintype "passive"))
      (node (ref "LED2") (pin "C") (pinfunction "C_C") (pintype "passive"))
      (node (ref "LED3") (pin "C") (pinfunction "C_C") (pintype "passive"))
      (node (ref "LED4") (pin "C") (pinfunction "C_C") (pintype "passive"))
      (node (ref "LED5") (pin "C") (pinfunction "C_C") (pintype "passive"))
      (node (ref "LED6") (pin "C") (pinfunction "C_C") (pintype "passive"))
      (node (ref "LED7") (pin "C") (pinfunction "C_C") (pintype "passive"))
      (node (ref "LED8") (pin "C") (pinfunction "C_C") (pintype "passive"))
      (node (ref "LED9") (pin "C") (pinfunction "C_C") (pintype "passive"))
      (node (ref "PROG.") (pin "3") (pinfunction "S_3") (pintype "passive"))
      (node (ref "Q1") (pin "2") (pinfunction "S_2") (pintype "passive"))
      (node (ref "Q2") (pin "2") (pinfunction "S_2") (pintype "passive"))
      (node (ref "Q3") (pin "2") (pinfunction "S_2") (pintype "passive"))
      (node (ref "Q4") (pin "2") (pinfunction "S_2") (pintype "passive"))
      (node (ref "R11") (pin "1") (pinfunction "1_1") (pintype "passive"))
      (node (ref "R19") (pin "2") (pinfunction "2_2") (pintype "passive"))
      (node (ref "R20") (pin "2") (pinfunction "2_2") (pintype "passive"))
      (node (ref "R3") (pin "1") (pinfunction "1_1") (pintype "passive"))
      (node (ref "R5") (pin "1") (pinfunction "1_1") (pintype "passive"))
      (node (ref "R9") (pin "1") (pinfunction "1_1") (pintype "passive"))
      (node (ref "U$1") (pin "P8.1") (pinfunction "DGND_P8.1") (pintype "bidirectional"))
      (node (ref "U$1") (pin "P8.2") (pinfunction "DGND_P8.2") (pintype "bidirectional"))
      (node (ref "U$1") (pin "P9.1") (pinfunction "DGND_P9.1") (pintype "bidirectional"))
      (node (ref "U$1") (pin "P9.2") (pinfunction "DGND_P9.2") (pintype "bidirectional"))
      (node (ref "U$1") (pin "P9.43") (pinfunction "DGND_P9.43") (pintype "bidirectional"))
      (node (ref "U$1") (pin "P9.44") (pinfunction "DGND_P9.44") (pintype "bidirectional"))
      (node (ref "U$1") (pin "P9.45") (pinfunction "DGND_P9.45") (pintype "bidirectional"))
      (node (ref "U$1") (pin "P9.46") (pinfunction "DGND_P9.46") (pintype "bidirectional"))
      (node (ref "U$2") (pin "6") (pinfunction "GND_2_6") (pintype "passive"))
      (node (ref "U$2") (pin "9") (pinfunction "PWPD_9") (pintype "passive"))
      (node (ref "U$4") (pin "6") (pinfunction "GND_2_6") (pintype "passive"))
      (node (ref "U$4") (pin "9") (pinfunction "PWPD_9") (pintype "passive"))
      (node (ref "U$5") (pin "P$1") (pinfunction "P1_P$1") (pintype "bidirectional"))
      (node (ref "U$5") (pin "P$4") (pinfunction "P4_P$4") (pintype "bidirectional"))
      (node (ref "U1") (pin "6") (pinfunction "GND_2_6") (pintype "passive"))
      (node (ref "U1") (pin "9") (pinfunction "PWPD_9") (pintype "passive"))
      (node (ref "U2") (pin "6") (pinfunction "GND_2_6") (pintype "passive"))
      (node (ref "U2") (pin "9") (pinfunction "PWPD_9") (pintype "passive"))
    )
    (net (code "19") (name "IO3") (class "Default")
      (node (ref "IC3") (pin "7") (pinfunction "OSC2/CLKO/RA6_7") (pintype "bidirectional"))
      (node (ref "R21") (pin "2") (pinfunction "2_2") (pintype "passive"))
    )
    (net (code "20") (name "IO3(1)") (class "Default")
      (node (ref "IC1") (pin "7") (pinfunction "OSC2/CLKO/RA6_7") (pintype "bidirectional"))
    )
    (net (code "21") (name "IO4") (class "Default")
      (node (ref "IC1") (pin "9") (pinfunction "RC1/CCP8/T1OSI/~{UOE}/RP12_9") (pintype "bidirectional"))
      (node (ref "IC3") (pin "9") (pinfunction "RC1/CCP8/T1OSI/~{UOE}/RP12_9") (pintype "bidirectional"))
      (node (ref "R25") (pin "2") (pinfunction "2_2") (pintype "passive"))
    )
    (net (code "22") (name "IO5") (class "Default")
      (node (ref "IC3") (pin "11") (pinfunction "VUSB_11") (pintype "input"))
      (node (ref "R24") (pin "2") (pinfunction "2_2") (pintype "passive"))
    )
    (net (code "23") (name "IO5(1)") (class "Default")
      (node (ref "IC1") (pin "11") (pinfunction "VUSB_11") (pintype "input"))
    )
    (net (code "24") (name "IO6") (class "Default")
      (node (ref "IC1") (pin "12") (pinfunction "RC4/D-/VM_12") (pintype "bidirectional"))
      (node (ref "IC3") (pin "12") (pinfunction "RC4/D-/VM_12") (pintype "bidirectional"))
      (node (ref "R22") (pin "2") (pinfunction "2_2") (pintype "passive"))
    )
    (net (code "25") (name "IO7") (class "Default")
      (node (ref "IC3") (pin "13") (pinfunction "RC5/D+/VP_13") (pintype "bidirectional"))
      (node (ref "R23") (pin "2") (pinfunction "2_2") (pintype "passive"))
    )
    (net (code "26") (name "IO7(1)") (class "Default")
      (node (ref "IC1") (pin "13") (pinfunction "RC5/D+/VP_13") (pintype "bidirectional"))
    )
    (net (code "27") (name "IO8") (class "Default")
      (node (ref "IC3") (pin "28") (pinfunction "RA1/AN1/C2INA/VBG/RP1_28") (pintype "bidirectional"))
    )
    (net (code "28") (name "IO8(1)") (class "Default")
      (node (ref "IC1") (pin "28") (pinfunction "RA1/AN1/C2INA/VBG/RP1_28") (pintype "bidirectional"))
    )
    (net (code "29") (name "LVP") (class "Default")
      (node (ref "PROG.") (pin "6") (pinfunction "S_6") (pintype "passive"))
    )
    (net (code "30") (name "MCLR") (class "Default")
      (node (ref "C21") (pin "1") (pinfunction "1_1") (pintype "passive"))
      (node (ref "PROG.") (pin "1") (pinfunction "S_1") (pintype "passive"))
      (node (ref "R13") (pin "2") (pinfunction "2_2") (pintype "passive"))
      (node (ref "R14") (pin "1") (pinfunction "1_1") (pintype "passive"))
      (node (ref "U$5") (pin "P$2") (pinfunction "P2_P$2") (pintype "bidirectional"))
      (node (ref "U$5") (pin "P$3") (pinfunction "P3_P$3") (pintype "bidirectional"))
    )
    (net (code "31") (name "MCLR'") (class "Default")
      (node (ref "IC3") (pin "26") (pinfunction "~{MCLR}_26") (pintype "input"))
      (node (ref "R13") (pin "1") (pinfunction "1_1") (pintype "passive"))
    )
    (net (code "32") (name "MCLR'(1)") (class "Default")
      (node (ref "IC1") (pin "26") (pinfunction "~{MCLR}_26") (pintype "input"))
    )
    (net (code "33") (name "N$19") (class "Default")
      (node (ref "IC2") (pin "8") (pinfunction "8_8") (pintype "passive"))
    )
    (net (code "34") (name "N$20") (class "Default")
      (node (ref "IC2") (pin "16") (pinfunction "16_16") (pintype "passive"))
    )
    (net (code "35") (name "N$25") (class "Default")
      (node (ref "IC1") (pin "8") (pinfunction "RC0/T1OSO/T1CKI/RP11_8") (pintype "bidirectional"))
      (node (ref "IC3") (pin "8") (pinfunction "RC0/T1OSO/T1CKI/RP11_8") (pintype "bidirectional"))
    )
    (net (code "36") (name "N$31") (class "Default")
      (node (ref "IC1") (pin "14") (pinfunction "RC6/CCP9/TX1/CK1/RP17_14") (pintype "bidirectional"))
      (node (ref "IC3") (pin "14") (pinfunction "RC6/CCP9/TX1/CK1/RP17_14") (pintype "bidirectional"))
    )
    (net (code "37") (name "Net-(D5-PadA)") (class "Default")
      (node (ref "D5") (pin "A") (pinfunction "A_A") (pintype "passive"))
      (node (ref "R15") (pin "2") (pinfunction "2_2") (pintype "passive"))
    )
    (net (code "38") (name "Net-(D6-PadA)") (class "Default")
      (node (ref "D6") (pin "A") (pinfunction "A_A") (pintype "passive"))
      (node (ref "R16") (pin "1") (pinfunction "1_1") (pintype "passive"))
    )
    (net (code "39") (name "Net-(LED1-PadA)") (class "Default")
      (node (ref "LED1") (pin "A") (pinfunction "A_A") (pintype "passive"))
      (node (ref "R6") (pin "1") (pinfunction "1_1") (pintype "passive"))
    )
    (net (code "40") (name "Net-(LED2-PadA)") (class "Default")
      (node (ref "LED2") (pin "A") (pinfunction "A_A") (pintype "passive"))
      (node (ref "R10") (pin "1") (pinfunction "1_1") (pintype "passive"))
    )
    (net (code "41") (name "Net-(LED3-PadA)") (class "Default")
      (node (ref "LED3") (pin "A") (pinfunction "A_A") (pintype "passive"))
      (node (ref "R12") (pin "1") (pinfunction "1_1") (pintype "passive"))
    )
    (net (code "42") (name "Net-(LED4-PadA)") (class "Default")
      (node (ref "LED4") (pin "A") (pinfunction "A_A") (pintype "passive"))
      (node (ref "R4") (pin "1") (pinfunction "1_1") (pintype "passive"))
    )
    (net (code "43") (name "Net-(LED5-PadA)") (class "Default")
      (node (ref "LED5") (pin "A") (pinfunction "A_A") (pintype "passive"))
      (node (ref "R21") (pin "1") (pinfunction "1_1") (pintype "passive"))
    )
    (net (code "44") (name "Net-(LED6-PadA)") (class "Default")
      (node (ref "LED6") (pin "A") (pinfunction "A_A") (pintype "passive"))
      (node (ref "R22") (pin "1") (pinfunction "1_1") (pintype "passive"))
    )
    (net (code "45") (name "Net-(LED7-PadA)") (class "Default")
      (node (ref "LED7") (pin "A") (pinfunction "A_A") (pintype "passive"))
      (node (ref "R23") (pin "1") (pinfunction "1_1") (pintype "passive"))
    )
    (net (code "46") (name "Net-(LED8-PadA)") (class "Default")
      (node (ref "LED8") (pin "A") (pinfunction "A_A") (pintype "passive"))
      (node (ref "R24") (pin "1") (pinfunction "1_1") (pintype "passive"))
    )
    (net (code "47") (name "Net-(LED9-PadA)") (class "Default")
      (node (ref "LED9") (pin "A") (pinfunction "A_A") (pintype "passive"))
      (node (ref "R25") (pin "1") (pinfunction "1_1") (pintype "passive"))
    )
    (net (code "48") (name "Net-(U$2-VSNS)") (class "Default")
      (node (ref "R1") (pin "1") (pinfunction "1_1") (pintype "passive"))
      (node (ref "R5") (pin "2") (pinfunction "2_2") (pintype "passive"))
      (node (ref "U$2") (pin "4") (pinfunction "VSNS_4") (pintype "passive"))
    )
    (net (code "49") (name "Net-(U$4-VSNS)") (class "Default")
      (node (ref "R11") (pin "2") (pinfunction "2_2") (pintype "passive"))
      (node (ref "R7") (pin "1") (pinfunction "1_1") (pintype "passive"))
      (node (ref "U$4") (pin "4") (pinfunction "VSNS_4") (pintype "passive"))
    )
    (net (code "50") (name "Net-(U1-VSNS)") (class "Default")
      (node (ref "R2") (pin "1") (pinfunction "1_1") (pintype "passive"))
      (node (ref "R3") (pin "2") (pinfunction "2_2") (pintype "passive"))
      (node (ref "U1") (pin "4") (pinfunction "VSNS_4") (pintype "passive"))
    )
    (net (code "51") (name "Net-(U2-VSNS)") (class "Default")
      (node (ref "R8") (pin "1") (pinfunction "1_1") (pintype "passive"))
      (node (ref "R9") (pin "2") (pinfunction "2_2") (pintype "passive"))
      (node (ref "U2") (pin "4") (pinfunction "VSNS_4") (pintype "passive"))
    )
    (net (code "52") (name "OC1") (class "Default")
      (node (ref "IC1") (pin "23") (pinfunction "RB5/CCP5/KBI1/SDI1/SDA1/RP8_23") (pintype "bidirectional"))
      (node (ref "IC3") (pin "23") (pinfunction "RB5/CCP5/KBI1/SDI1/SDA1/RP8_23") (pintype "bidirectional"))
      (node (ref "J2") (pin "1") (pinfunction "S_1") (pintype "passive"))
    )
    (net (code "53") (name "OC2") (class "Default")
      (node (ref "IC1") (pin "22") (pinfunction "RB4/CCP4/KBI0/SCK1/SCL1/RP7_22") (pintype "bidirectional"))
      (node (ref "IC3") (pin "22") (pinfunction "RB4/CCP4/KBI0/SCK1/SCL1/RP7_22") (pintype "bidirectional"))
      (node (ref "J1") (pin "1") (pinfunction "S_1") (pintype "passive"))
    )
    (net (code "54") (name "OC3") (class "Default")
      (node (ref "IC1") (pin "21") (pinfunction "RB3/AN9/C3INA/CTED2/VPO/RP6_21") (pintype "bidirectional"))
      (node (ref "IC3") (pin "21") (pinfunction "RB3/AN9/C3INA/CTED2/VPO/RP6_21") (pintype "bidirectional"))
      (node (ref "J3") (pin "1") (pinfunction "S_1") (pintype "passive"))
    )
    (net (code "55") (name "OC4") (class "Default")
      (node (ref "IC3") (pin "19") (pinfunction "RB1/AN10/C3INC/RTCC/RP4_19") (pintype "bidirectional"))
      (node (ref "J4") (pin "1") (pinfunction "S_1") (pintype "passive"))
    )
    (net (code "56") (name "OC4(1)") (class "Default")
      (node (ref "IC1") (pin "19") (pinfunction "RB1/AN10/C3INC/RTCC/RP4_19") (pintype "bidirectional"))
    )
    (net (code "57") (name "OC5") (class "Default")
      (node (ref "IC3") (pin "18") (pinfunction "RB0/AN12/C3IND/INT0/RP3_18") (pintype "bidirectional"))
      (node (ref "J5") (pin "1") (pinfunction "S_1") (pintype "passive"))
    )
    (net (code "58") (name "OC5(1)") (class "Default")
      (node (ref "IC1") (pin "18") (pinfunction "RB0/AN12/C3IND/INT0/RP3_18") (pintype "bidirectional"))
    )
    (net (code "59") (name "OC6") (class "Default")
      (node (ref "IC3") (pin "15") (pinfunction "RC7/CCP10/RX1/DT1/SDO1/RP18_15") (pintype "bidirectional"))
      (node (ref "J6") (pin "1") (pinfunction "S_1") (pintype "passive"))
    )
    (net (code "60") (name "OC6(1)") (class "Default")
      (node (ref "IC1") (pin "15") (pinfunction "RC7/CCP10/RX1/DT1/SDO1/RP18_15") (pintype "bidirectional"))
    )
    (net (code "61") (name "PGC1") (class "Default")
      (node (ref "IC3") (pin "2") (pinfunction "RA3/AN3/C1INB/VREF+_2") (pintype "bidirectional"))
      (node (ref "PROG.") (pin "5") (pinfunction "S_5") (pintype "passive"))
    )
    (net (code "62") (name "PGC1(1)") (class "Default")
      (node (ref "IC1") (pin "2") (pinfunction "RA3/AN3/C1INB/VREF+_2") (pintype "bidirectional"))
    )
    (net (code "63") (name "PGD1") (class "Default")
      (node (ref "IC3") (pin "1") (pinfunction "RA2/AN2/C2INB/C1IND/C3INB/VREF-/CVREF_1") (pintype "bidirectional"))
      (node (ref "PROG.") (pin "4") (pinfunction "S_4") (pintype "passive"))
    )
    (net (code "64") (name "PGD1(1)") (class "Default")
      (node (ref "IC1") (pin "1") (pinfunction "RA2/AN2/C2INB/C1IND/C3INB/VREF-/CVREF_1") (pintype "bidirectional"))
    )
    (net (code "65") (name "PH_5") (class "Default")
      (node (ref "C17") (pin "2") (pinfunction "2_2") (pintype "passive"))
      (node (ref "C5") (pin "2") (pinfunction "2_2") (pintype "passive"))
      (node (ref "D1") (pin "3") (pinfunction "K_3") (pintype "passive"))
      (node (ref "D2") (pin "3") (pinfunction "K_3") (pintype "passive"))
      (node (ref "L1") (pin "1") (pinfunction "1_1") (pintype "passive"))
      (node (ref "L2") (pin "1") (pinfunction "1_1") (pintype "passive"))
      (node (ref "U$2") (pin "8") (pinfunction "PH_8") (pintype "passive"))
      (node (ref "U1") (pin "8") (pinfunction "PH_8") (pintype "passive"))
    )
    (net (code "66") (name "PH_MOTOR") (class "Default")
      (node (ref "C11") (pin "2") (pinfunction "2_2") (pintype "passive"))
      (node (ref "C20'") (pin "2") (pinfunction "2_2") (pintype "passive"))
      (node (ref "D3") (pin "3") (pinfunction "K_3") (pintype "passive"))
      (node (ref "D4") (pin "3") (pinfunction "K_3") (pintype "passive"))
      (node (ref "L3") (pin "1") (pinfunction "1_1") (pintype "passive"))
      (node (ref "L4") (pin "1") (pinfunction "1_1") (pintype "passive"))
      (node (ref "U$4") (pin "8") (pinfunction "PH_8") (pintype "passive"))
      (node (ref "U2") (pin "8") (pinfunction "PH_8") (pintype "passive"))
    )
    (net (code "67") (name "POWER_EN(1)") (class "Default")
      (node (ref "Q1") (pin "1") (pinfunction "G_1") (pintype "passive"))
    )
    (net (code "68") (name "POWER_EN(2)") (class "Default")
      (node (ref "Q3") (pin "1") (pinfunction "G_1") (pintype "passive"))
    )
    (net (code "69") (name "POWER_EN(3)") (class "Default")
      (node (ref "Q2") (pin "1") (pinfunction "G_1") (pintype "passive"))
    )
    (net (code "70") (name "POWER_EN(4)") (class "Default")
      (node (ref "Q4") (pin "1") (pinfunction "G_1") (pintype "passive"))
    )
    (net (code "71") (name "SCL") (class "Default")
      (node (ref "IC1") (pin "4") (pinfunction "RA5/AN4/C1INC/~{SS1}/HLVDIN/RCV/RP2_4") (pintype "bidirectional"))
      (node (ref "IC3") (pin "4") (pinfunction "RA5/AN4/C1INC/~{SS1}/HLVDIN/RCV/RP2_4") (pintype "bidirectional"))
      (node (ref "U$1") (pin "P9.19") (pinfunction "I2C2_SCL_P9.19") (pintype "bidirectional"))
    )
    (net (code "72") (name "SDA") (class "Default")
      (node (ref "IC1") (pin "3") (pinfunction "VDDCORE/VCAP_3") (pintype "input"))
      (node (ref "IC3") (pin "3") (pinfunction "VDDCORE/VCAP_3") (pintype "input"))
      (node (ref "U$1") (pin "P9.20") (pinfunction "I2C2_SDA_P9.20") (pintype "bidirectional"))
    )
    (net (code "73") (name "SWITCH_1") (class "Default")
      (node (ref "IC3") (pin "27") (pinfunction "RA0/AN0/C1INA/ULPWU/RP0_27") (pintype "bidirectional"))
      (node (ref "R19") (pin "1") (pinfunction "1_1") (pintype "passive"))
      (node (ref "U$6") (pin "P$2") (pinfunction "P2_P$2") (pintype "bidirectional"))
      (node (ref "U$6") (pin "P$3") (pinfunction "P3_P$3") (pintype "bidirectional"))
    )
    (net (code "74") (name "SWITCH_2") (class "Default")
      (node (ref "IC3") (pin "6") (pinfunction "OSC1/CLKI/RA7_6") (pintype "bidirectional"))
      (node (ref "R20") (pin "1") (pinfunction "1_1") (pintype "passive"))
      (node (ref "U$7") (pin "P$2") (pinfunction "P2_P$2") (pintype "bidirectional"))
      (node (ref "U$7") (pin "P$3") (pinfunction "P3_P$3") (pintype "bidirectional"))
    )
    (net (code "75") (name "VCC") (class "Default")
      (node (ref "C1") (pin "2") (pinfunction "2_2") (pintype "passive"))
      (node (ref "C10") (pin "2") (pinfunction "2_2") (pintype "passive"))
      (node (ref "C13") (pin "2") (pinfunction "2_2") (pintype "passive"))
      (node (ref "C14") (pin "2") (pinfunction "2_2") (pintype "passive"))
      (node (ref "C15") (pin "2") (pinfunction "2_2") (pintype "passive"))
      (node (ref "C16") (pin "2") (pinfunction "2_2") (pintype "passive"))
      (node (ref "C19") (pin "2") (pinfunction "2_2") (pintype "passive"))
      (node (ref "C19'") (pin "2") (pinfunction "2_2") (pintype "passive"))
      (node (ref "C2") (pin "2") (pinfunction "2_2") (pintype "passive"))
      (node (ref "C20") (pin "2") (pinfunction "2_2") (pintype "passive"))
      (node (ref "C22") (pin "2") (pinfunction "2_2") (pintype "passive"))
      (node (ref "C3") (pin "2") (pinfunction "2_2") (pintype "passive"))
      (node (ref "C4") (pin "2") (pinfunction "2_2") (pintype "passive"))
      (node (ref "C7") (pin "2") (pinfunction "2_2") (pintype "passive"))
      (node (ref "C8") (pin "2") (pinfunction "2_2") (pintype "passive"))
      (node (ref "C9") (pin "2") (pinfunction "2_2") (pintype "passive"))
      (node (ref "U$2") (pin "7") (pinfunction "VIN_7") (pintype "passive"))
      (node (ref "U$4") (pin "7") (pinfunction "VIN_7") (pintype "passive"))
      (node (ref "U1") (pin "7") (pinfunction "VIN_7") (pintype "passive"))
      (node (ref "U2") (pin "7") (pinfunction "VIN_7") (pintype "passive"))
    )
    (net (code "76") (name "VOUT_LOGIC") (class "Default")
      (node (ref "C12") (pin "1") (pinfunction "+_1") (pintype "passive"))
      (node (ref "L3") (pin "2") (pinfunction "2_2") (pintype "passive"))
      (node (ref "R10") (pin "2") (pinfunction "2_2") (pintype "passive"))
      (node (ref "R8") (pin "2") (pinfunction "2_2") (pintype "passive"))
    )
    (net (code "77") (name "VOUT_MOTOR") (class "Default")
      (node (ref "C18") (pin "1") (pinfunction "+_1") (pintype "passive"))
      (node (ref "J13") (pin "2") (pinfunction "S_2") (pintype "passive"))
      (node (ref "J13") (pin "3") (pinfunction "S_3") (pintype "passive"))
      (node (ref "L2") (pin "2") (pinfunction "2_2") (pintype "passive"))
      (node (ref "R1") (pin "2") (pinfunction "2_2") (pintype "passive"))
      (node (ref "R6") (pin "2") (pinfunction "2_2") (pintype "passive"))
    )
    (net (code "78") (name "VOUT_SERVOLEFT") (class "Default")
      (node (ref "C28") (pin "1") (pinfunction "1_1") (pintype "passive"))
      (node (ref "C6") (pin "1") (pinfunction "+_1") (pintype "passive"))
      (node (ref "J4") (pin "2") (pinfunction "S_2") (pintype "passive"))
      (node (ref "J5") (pin "2") (pinfunction "S_2") (pintype "passive"))
      (node (ref "J6") (pin "2") (pinfunction "S_2") (pintype "passive"))
      (node (ref "L1") (pin "2") (pinfunction "2_2") (pintype "passive"))
      (node (ref "R2") (pin "2") (pinfunction "2_2") (pintype "passive"))
      (node (ref "R4") (pin "2") (pinfunction "2_2") (pintype "passive"))
    )
    (net (code "79") (name "VOUT_SERVORIGHT") (class "Default")
      (node (ref "C21'") (pin "1") (pinfunction "+_1") (pintype "passive"))
      (node (ref "C27") (pin "1") (pinfunction "1_1") (pintype "passive"))
      (node (ref "J1") (pin "2") (pinfunction "S_2") (pintype "passive"))
      (node (ref "J2") (pin "2") (pinfunction "S_2") (pintype "passive"))
      (node (ref "J3") (pin "2") (pinfunction "S_2") (pintype "passive"))
      (node (ref "L4") (pin "2") (pinfunction "2_2") (pintype "passive"))
      (node (ref "R12") (pin "2") (pinfunction "2_2") (pintype "passive"))
      (node (ref "R7") (pin "2") (pinfunction "2_2") (pintype "passive"))
    )
    (net (code "80") (name "VSS") (class "Default")
      (node (ref "C23") (pin "C") (pinfunction "-_C") (pintype "passive"))
      (node (ref "C24") (pin "C") (pinfunction "-_C") (pintype "passive"))
      (node (ref "C27") (pin "2") (pinfunction "2_2") (pintype "passive"))
      (node (ref "C28") (pin "2") (pinfunction "2_2") (pintype "passive"))
      (node (ref "D5") (pin "C") (pinfunction "C_C") (pintype "passive"))
      (node (ref "D6") (pin "C") (pinfunction "C_C") (pintype "passive"))
      (node (ref "J1") (pin "3") (pinfunction "S_3") (pintype "passive"))
      (node (ref "J2") (pin "3") (pinfunction "S_3") (pintype "passive"))
      (node (ref "J3") (pin "3") (pinfunction "S_3") (pintype "passive"))
      (node (ref "J4") (pin "3") (pinfunction "S_3") (pintype "passive"))
      (node (ref "J5") (pin "3") (pinfunction "S_3") (pintype "passive"))
      (node (ref "J6") (pin "3") (pinfunction "S_3") (pintype "passive"))
      (node (ref "U3") (pin "1") (pinfunction "GND_1") (pintype "passive"))
    )
    (net (code "81") (name "unconnected-(IC1-OSC1{slash}CLKI{slash}RA7-Pad6)") (class "Default")
      (node (ref "IC1") (pin "6") (pinfunction "OSC1/CLKI/RA7_6") (pintype "bidirectional"))
    )
    (net (code "82") (name "unconnected-(IC1-RA0{slash}AN0{slash}C1INA{slash}ULPWU{slash}RP0-Pad27)") (class "Default")
      (node (ref "IC1") (pin "27") (pinfunction "RA0/AN0/C1INA/ULPWU/RP0_27") (pintype "bidirectional"))
    )
    (net (code "83") (name "unconnected-(IC1-RB2{slash}AN8{slash}C2INC{slash}CTED1{slash}VMO{slash}REFO{slash}RP5-Pad20)") (class "Default")
      (node (ref "IC1") (pin "20") (pinfunction "RB2/AN8/C2INC/CTED1/VMO/REFO/RP5_20") (pintype "bidirectional"))
    )
    (net (code "84") (name "unconnected-(IC1-VDD-Pad17)") (class "Default")
      (node (ref "IC1") (pin "17") (pinfunction "VDD_17") (pintype "input"))
    )
    (net (code "85") (name "unconnected-(IC1-VSS2-Pad16)") (class "Default")
      (node (ref "IC1") (pin "16") (pinfunction "VSS2_16") (pintype "input"))
    )
    (net (code "86") (name "unconnected-(IC3-RB2{slash}AN8{slash}C2INC{slash}CTED1{slash}VMO{slash}REFO{slash}RP5-Pad20)") (class "Default")
      (node (ref "IC3") (pin "20") (pinfunction "RB2/AN8/C2INC/CTED1/VMO/REFO/RP5_20") (pintype "bidirectional"))
    )
    (net (code "87") (name "unconnected-(IC3-VDD-Pad17)") (class "Default")
      (node (ref "IC3") (pin "17") (pinfunction "VDD_17") (pintype "input"))
    )
    (net (code "88") (name "unconnected-(IC3-VSS2-Pad16)") (class "Default")
      (node (ref "IC3") (pin "16") (pinfunction "VSS2_16") (pintype "input"))
    )
    (net (code "89") (name "unconnected-(J7A-S-Pad1)") (class "Default")
      (node (ref "J7") (pin "1") (pinfunction "S_1") (pintype "passive"))
    )
    (net (code "90") (name "unconnected-(J7B-S-Pad2)") (class "Default")
      (node (ref "J7") (pin "2") (pinfunction "S_2") (pintype "passive"))
    )
    (net (code "91") (name "unconnected-(J8A-S-Pad1)") (class "Default")
      (node (ref "J8") (pin "1") (pinfunction "S_1") (pintype "passive"))
    )
    (net (code "92") (name "unconnected-(J8B-S-Pad2)") (class "Default")
      (node (ref "J8") (pin "2") (pinfunction "S_2") (pintype "passive"))
    )
    (net (code "93") (name "unconnected-(J9A-S-Pad1)") (class "Default")
      (node (ref "J9") (pin "1") (pinfunction "S_1") (pintype "passive"))
    )
    (net (code "94") (name "unconnected-(J9B-S-Pad2)") (class "Default")
      (node (ref "J9") (pin "2") (pinfunction "S_2") (pintype "passive"))
    )
    (net (code "95") (name "unconnected-(J10A-S-Pad1)") (class "Default")
      (node (ref "J10") (pin "1") (pinfunction "S_1") (pintype "passive"))
    )
    (net (code "96") (name "unconnected-(J10B-S-Pad2)") (class "Default")
      (node (ref "J10") (pin "2") (pinfunction "S_2") (pintype "passive"))
    )
    (net (code "97") (name "unconnected-(J11A-S-Pad1)") (class "Default")
      (node (ref "J11") (pin "1") (pinfunction "S_1") (pintype "passive"))
    )
    (net (code "98") (name "unconnected-(J11B-S-Pad2)") (class "Default")
      (node (ref "J11") (pin "2") (pinfunction "S_2") (pintype "passive"))
    )
    (net (code "99") (name "unconnected-(J12A-S-Pad1)") (class "Default")
      (node (ref "J12") (pin "1") (pinfunction "S_1") (pintype "passive"))
    )
    (net (code "100") (name "unconnected-(J12B-S-Pad2)") (class "Default")
      (node (ref "J12") (pin "2") (pinfunction "S_2") (pintype "passive"))
    )
    (net (code "101") (name "unconnected-(U$1A-GPIO_8-PadP8.35)") (class "Default")
      (node (ref "U$1") (pin "P8.35") (pinfunction "GPIO_8_P8.35") (pintype "bidirectional"))
    )
    (net (code "102") (name "unconnected-(U$1A-GPIO_9-PadP8.33)") (class "Default")
      (node (ref "U$1") (pin "P8.33") (pinfunction "GPIO_9_P8.33") (pintype "bidirectional"))
    )
    (net (code "103") (name "unconnected-(U$1A-GPIO_10-PadP8.31)") (class "Default")
      (node (ref "U$1") (pin "P8.31") (pinfunction "GPIO_10_P8.31") (pintype "bidirectional"))
    )
    (net (code "104") (name "unconnected-(U$1A-GPIO_11-PadP8.32)") (class "Default")
      (node (ref "U$1") (pin "P8.32") (pinfunction "GPIO_11_P8.32") (pintype "bidirectional"))
    )
    (net (code "105") (name "unconnected-(U$1A-GPIO_22-PadP8.19)") (class "Default")
      (node (ref "U$1") (pin "P8.19") (pinfunction "GPIO_22_P8.19") (pintype "bidirectional"))
    )
    (net (code "106") (name "unconnected-(U$1A-GPIO_23-PadP8.13)") (class "Default")
      (node (ref "U$1") (pin "P8.13") (pinfunction "GPIO_23_P8.13") (pintype "bidirectional"))
    )
    (net (code "107") (name "unconnected-(U$1A-GPIO_26-PadP8.14)") (class "Default")
      (node (ref "U$1") (pin "P8.14") (pinfunction "GPIO_26_P8.14") (pintype "bidirectional"))
    )
    (net (code "108") (name "unconnected-(U$1A-GPIO_27-PadP8.17)") (class "Default")
      (node (ref "U$1") (pin "P8.17") (pinfunction "GPIO_27_P8.17") (pintype "bidirectional"))
    )
    (net (code "109") (name "unconnected-(U$1A-GPIO_32-PadP8.25)") (class "Default")
      (node (ref "U$1") (pin "P8.25") (pinfunction "GPIO_32_P8.25") (pintype "bidirectional"))
    )
    (net (code "110") (name "unconnected-(U$1A-GPIO_33-PadP8.24)") (class "Default")
      (node (ref "U$1") (pin "P8.24") (pinfunction "GPIO_33_P8.24") (pintype "bidirectional"))
    )
    (net (code "111") (name "unconnected-(U$1A-GPIO_34-PadP8.5)") (class "Default")
      (node (ref "U$1") (pin "P8.5") (pinfunction "GPIO_34_P8.5") (pintype "bidirectional"))
    )
    (net (code "112") (name "unconnected-(U$1A-GPIO_35-PadP8.6)") (class "Default")
      (node (ref "U$1") (pin "P8.6") (pinfunction "GPIO_35_P8.6") (pintype "bidirectional"))
    )
    (net (code "113") (name "unconnected-(U$1A-GPIO_36-PadP8.23)") (class "Default")
      (node (ref "U$1") (pin "P8.23") (pinfunction "GPIO_36_P8.23") (pintype "bidirectional"))
    )
    (net (code "114") (name "unconnected-(U$1A-GPIO_37-PadP8.22)") (class "Default")
      (node (ref "U$1") (pin "P8.22") (pinfunction "GPIO_37_P8.22") (pintype "bidirectional"))
    )
    (net (code "115") (name "unconnected-(U$1A-GPIO_38-PadP8.3)") (class "Default")
      (node (ref "U$1") (pin "P8.3") (pinfunction "GPIO_38_P8.3") (pintype "bidirectional"))
    )
    (net (code "116") (name "unconnected-(U$1A-GPIO_39-PadP8.4)") (class "Default")
      (node (ref "U$1") (pin "P8.4") (pinfunction "GPIO_39_P8.4") (pintype "bidirectional"))
    )
    (net (code "117") (name "unconnected-(U$1A-GPIO_44-PadP8.12)") (class "Default")
      (node (ref "U$1") (pin "P8.12") (pinfunction "GPIO_44_P8.12") (pintype "bidirectional"))
    )
    (net (code "118") (name "unconnected-(U$1A-GPIO_45-PadP8.11)") (class "Default")
      (node (ref "U$1") (pin "P8.11") (pinfunction "GPIO_45_P8.11") (pintype "bidirectional"))
    )
    (net (code "119") (name "unconnected-(U$1A-GPIO_46-PadP8.16)") (class "Default")
      (node (ref "U$1") (pin "P8.16") (pinfunction "GPIO_46_P8.16") (pintype "bidirectional"))
    )
    (net (code "120") (name "unconnected-(U$1A-GPIO_47-PadP8.15)") (class "Default")
      (node (ref "U$1") (pin "P8.15") (pinfunction "GPIO_47_P8.15") (pintype "bidirectional"))
    )
    (net (code "121") (name "unconnected-(U$1A-GPIO_61-PadP8.26)") (class "Default")
      (node (ref "U$1") (pin "P8.26") (pinfunction "GPIO_61_P8.26") (pintype "bidirectional"))
    )
    (net (code "122") (name "unconnected-(U$1A-GPIO_62-PadP8.21)") (class "Default")
      (node (ref "U$1") (pin "P8.21") (pinfunction "GPIO_62_P8.21") (pintype "bidirectional"))
    )
    (net (code "123") (name "unconnected-(U$1A-GPIO_63-PadP8.20)") (class "Default")
      (node (ref "U$1") (pin "P8.20") (pinfunction "GPIO_63_P8.20") (pintype "bidirectional"))
    )
    (net (code "124") (name "unconnected-(U$1A-GPIO_65-PadP8.18)") (class "Default")
      (node (ref "U$1") (pin "P8.18") (pinfunction "GPIO_65_P8.18") (pintype "bidirectional"))
    )
    (net (code "125") (name "unconnected-(U$1A-GPIO_66-PadP8.7)") (class "Default")
      (node (ref "U$1") (pin "P8.7") (pinfunction "GPIO_66_P8.7") (pintype "bidirectional"))
    )
    (net (code "126") (name "unconnected-(U$1A-GPIO_67-PadP8.8)") (class "Default")
      (node (ref "U$1") (pin "P8.8") (pinfunction "GPIO_67_P8.8") (pintype "bidirectional"))
    )
    (net (code "127") (name "unconnected-(U$1A-GPIO_68-PadP8.10)") (class "Default")
      (node (ref "U$1") (pin "P8.10") (pinfunction "GPIO_68_P8.10") (pintype "bidirectional"))
    )
    (net (code "128") (name "unconnected-(U$1A-GPIO_69-PadP8.9)") (class "Default")
      (node (ref "U$1") (pin "P8.9") (pinfunction "GPIO_69_P8.9") (pintype "bidirectional"))
    )
    (net (code "129") (name "unconnected-(U$1A-GPIO_70-PadP8.45)") (class "Default")
      (node (ref "U$1") (pin "P8.45") (pinfunction "GPIO_70_P8.45") (pintype "bidirectional"))
    )
    (net (code "130") (name "unconnected-(U$1A-GPIO_71-PadP8.46)") (class "Default")
      (node (ref "U$1") (pin "P8.46") (pinfunction "GPIO_71_P8.46") (pintype "bidirectional"))
    )
    (net (code "131") (name "unconnected-(U$1A-GPIO_72-PadP8.43)") (class "Default")
      (node (ref "U$1") (pin "P8.43") (pinfunction "GPIO_72_P8.43") (pintype "bidirectional"))
    )
    (net (code "132") (name "unconnected-(U$1A-GPIO_73-PadP8.44)") (class "Default")
      (node (ref "U$1") (pin "P8.44") (pinfunction "GPIO_73_P8.44") (pintype "bidirectional"))
    )
    (net (code "133") (name "unconnected-(U$1A-GPIO_74-PadP8.41)") (class "Default")
      (node (ref "U$1") (pin "P8.41") (pinfunction "GPIO_74_P8.41") (pintype "bidirectional"))
    )
    (net (code "134") (name "unconnected-(U$1A-GPIO_75-PadP8.42)") (class "Default")
      (node (ref "U$1") (pin "P8.42") (pinfunction "GPIO_75_P8.42") (pintype "bidirectional"))
    )
    (net (code "135") (name "unconnected-(U$1A-GPIO_76-PadP8.39)") (class "Default")
      (node (ref "U$1") (pin "P8.39") (pinfunction "GPIO_76_P8.39") (pintype "bidirectional"))
    )
    (net (code "136") (name "unconnected-(U$1A-GPIO_77-PadP8.40)") (class "Default")
      (node (ref "U$1") (pin "P8.40") (pinfunction "GPIO_77_P8.40") (pintype "bidirectional"))
    )
    (net (code "137") (name "unconnected-(U$1A-GPIO_78-PadP8.37)") (class "Default")
      (node (ref "U$1") (pin "P8.37") (pinfunction "GPIO_78_P8.37") (pintype "bidirectional"))
    )
    (net (code "138") (name "unconnected-(U$1A-GPIO_79-PadP8.38)") (class "Default")
      (node (ref "U$1") (pin "P8.38") (pinfunction "GPIO_79_P8.38") (pintype "bidirectional"))
    )
    (net (code "139") (name "unconnected-(U$1A-GPIO_80-PadP8.36)") (class "Default")
      (node (ref "U$1") (pin "P8.36") (pinfunction "GPIO_80_P8.36") (pintype "bidirectional"))
    )
    (net (code "140") (name "unconnected-(U$1A-GPIO_81-PadP8.34)") (class "Default")
      (node (ref "U$1") (pin "P8.34") (pinfunction "GPIO_81_P8.34") (pintype "bidirectional"))
    )
    (net (code "141") (name "unconnected-(U$1A-GPIO_86-PadP8.27)") (class "Default")
      (node (ref "U$1") (pin "P8.27") (pinfunction "GPIO_86_P8.27") (pintype "bidirectional"))
    )
    (net (code "142") (name "unconnected-(U$1A-GPIO_87-PadP8.29)") (class "Default")
      (node (ref "U$1") (pin "P8.29") (pinfunction "GPIO_87_P8.29") (pintype "bidirectional"))
    )
    (net (code "143") (name "unconnected-(U$1A-GPIO_88-PadP8.28)") (class "Default")
      (node (ref "U$1") (pin "P8.28") (pinfunction "GPIO_88_P8.28") (pintype "bidirectional"))
    )
    (net (code "144") (name "unconnected-(U$1A-GPIO_89-PadP8.30)") (class "Default")
      (node (ref "U$1") (pin "P8.30") (pinfunction "GPIO_89_P8.30") (pintype "bidirectional"))
    )
    (net (code "145") (name "unconnected-(U$1B-AIN0-PadP9.39)") (class "Default")
      (node (ref "U$1") (pin "P9.39") (pinfunction "AIN0_P9.39") (pintype "bidirectional"))
    )
    (net (code "146") (name "unconnected-(U$1B-AIN1-PadP9.40)") (class "Default")
      (node (ref "U$1") (pin "P9.40") (pinfunction "AIN1_P9.40") (pintype "bidirectional"))
    )
    (net (code "147") (name "unconnected-(U$1B-AIN2-PadP9.37)") (class "Default")
      (node (ref "U$1") (pin "P9.37") (pinfunction "AIN2_P9.37") (pintype "bidirectional"))
    )
    (net (code "148") (name "unconnected-(U$1B-AIN3-PadP9.38)") (class "Default")
      (node (ref "U$1") (pin "P9.38") (pinfunction "AIN3_P9.38") (pintype "bidirectional"))
    )
    (net (code "149") (name "unconnected-(U$1B-AIN4-PadP9.33)") (class "Default")
      (node (ref "U$1") (pin "P9.33") (pinfunction "AIN4_P9.33") (pintype "bidirectional"))
    )
    (net (code "150") (name "unconnected-(U$1B-AIN5-PadP9.36)") (class "Default")
      (node (ref "U$1") (pin "P9.36") (pinfunction "AIN5_P9.36") (pintype "bidirectional"))
    )
    (net (code "151") (name "unconnected-(U$1B-AIN6-PadP9.35)") (class "Default")
      (node (ref "U$1") (pin "P9.35") (pinfunction "AIN6_P9.35") (pintype "bidirectional"))
    )
    (net (code "152") (name "unconnected-(U$1B-GNDA_ADC-PadP9.34)") (class "Default")
      (node (ref "U$1") (pin "P9.34") (pinfunction "GNDA_ADC_P9.34") (pintype "bidirectional"))
    )
    (net (code "153") (name "unconnected-(U$1B-GPIO_2-PadP9.22)") (class "Default")
      (node (ref "U$1") (pin "P9.22") (pinfunction "GPIO_2_P9.22") (pintype "bidirectional"))
    )
    (net (code "154") (name "unconnected-(U$1B-GPIO_3-PadP9.21)") (class "Default")
      (node (ref "U$1") (pin "P9.21") (pinfunction "GPIO_3_P9.21") (pintype "bidirectional"))
    )
    (net (code "155") (name "unconnected-(U$1B-GPIO_4-PadP9.17)") (class "Default")
      (node (ref "U$1") (pin "P9.17") (pinfunction "GPIO_4_P9.17") (pintype "bidirectional"))
    )
    (net (code "156") (name "unconnected-(U$1B-GPIO_5-PadP9.18)") (class "Default")
      (node (ref "U$1") (pin "P9.18") (pinfunction "GPIO_5_P9.18") (pintype "bidirectional"))
    )
    (net (code "157") (name "unconnected-(U$1B-GPIO_7-PadP9.42)") (class "Default")
      (node (ref "U$1") (pin "P9.42") (pinfunction "GPIO_7_P9.42") (pintype "bidirectional"))
    )
    (net (code "158") (name "unconnected-(U$1B-GPIO_14-PadP9.26)") (class "Default")
      (node (ref "U$1") (pin "P9.26") (pinfunction "GPIO_14_P9.26") (pintype "bidirectional"))
    )
    (net (code "159") (name "unconnected-(U$1B-GPIO_15-PadP9.24)") (class "Default")
      (node (ref "U$1") (pin "P9.24") (pinfunction "GPIO_15_P9.24") (pintype "bidirectional"))
    )
    (net (code "160") (name "unconnected-(U$1B-GPIO_20-PadP9.41)") (class "Default")
      (node (ref "U$1") (pin "P9.41") (pinfunction "GPIO_20_P9.41") (pintype "bidirectional"))
    )
    (net (code "161") (name "unconnected-(U$1B-GPIO_30-PadP9.11)") (class "Default")
      (node (ref "U$1") (pin "P9.11") (pinfunction "GPIO_30_P9.11") (pintype "bidirectional"))
    )
    (net (code "162") (name "unconnected-(U$1B-GPIO_31-PadP9.13)") (class "Default")
      (node (ref "U$1") (pin "P9.13") (pinfunction "GPIO_31_P9.13") (pintype "bidirectional"))
    )
    (net (code "163") (name "unconnected-(U$1B-GPIO_40-PadP9.14)") (class "Default")
      (node (ref "U$1") (pin "P9.14") (pinfunction "GPIO_40_P9.14") (pintype "bidirectional"))
    )
    (net (code "164") (name "unconnected-(U$1B-GPIO_48-PadP9.15)") (class "Default")
      (node (ref "U$1") (pin "P9.15") (pinfunction "GPIO_48_P9.15") (pintype "bidirectional"))
    )
    (net (code "165") (name "unconnected-(U$1B-GPIO_49-PadP9.23)") (class "Default")
      (node (ref "U$1") (pin "P9.23") (pinfunction "GPIO_49_P9.23") (pintype "bidirectional"))
    )
    (net (code "166") (name "unconnected-(U$1B-GPIO_51-PadP9.16)") (class "Default")
      (node (ref "U$1") (pin "P9.16") (pinfunction "GPIO_51_P9.16") (pintype "bidirectional"))
    )
    (net (code "167") (name "unconnected-(U$1B-GPIO_60-PadP9.12)") (class "Default")
      (node (ref "U$1") (pin "P9.12") (pinfunction "GPIO_60_P9.12") (pintype "bidirectional"))
    )
    (net (code "168") (name "unconnected-(U$1B-GPIO_117-PadP9.25)") (class "Default")
      (node (ref "U$1") (pin "P9.25") (pinfunction "GPIO_117_P9.25") (pintype "bidirectional"))
    )
    (net (code "169") (name "unconnected-(U$1B-GPIO_120-PadP9.31)") (class "Default")
      (node (ref "U$1") (pin "P9.31") (pinfunction "GPIO_120_P9.31") (pintype "bidirectional"))
    )
    (net (code "170") (name "unconnected-(U$1B-GPIO_121-PadP9.29)") (class "Default")
      (node (ref "U$1") (pin "P9.29") (pinfunction "GPIO_121_P9.29") (pintype "bidirectional"))
    )
    (net (code "171") (name "unconnected-(U$1B-GPIO_122-PadP9.30)") (class "Default")
      (node (ref "U$1") (pin "P9.30") (pinfunction "GPIO_122_P9.30") (pintype "bidirectional"))
    )
    (net (code "172") (name "unconnected-(U$1B-GPIO_123-PadP9.28)") (class "Default")
      (node (ref "U$1") (pin "P9.28") (pinfunction "GPIO_123_P9.28") (pintype "bidirectional"))
    )
    (net (code "173") (name "unconnected-(U$1B-GPIO_125-PadP9.27)") (class "Default")
      (node (ref "U$1") (pin "P9.27") (pinfunction "GPIO_125_P9.27") (pintype "bidirectional"))
    )
    (net (code "174") (name "unconnected-(U$1B-PWR_BUT-PadP9.9)") (class "Default")
      (node (ref "U$1") (pin "P9.9") (pinfunction "PWR_BUT_P9.9") (pintype "bidirectional"))
    )
    (net (code "175") (name "unconnected-(U$1B-SYS_5V-PadP9.7)") (class "Default")
      (node (ref "U$1") (pin "P9.7") (pinfunction "SYS_5V_P9.7") (pintype "bidirectional"))
    )
    (net (code "176") (name "unconnected-(U$1B-SYS_5V-PadP9.8)") (class "Default")
      (node (ref "U$1") (pin "P9.8") (pinfunction "SYS_5V_P9.8") (pintype "bidirectional"))
    )
    (net (code "177") (name "unconnected-(U$1B-SYS_RESET~{N}-PadP9.10)") (class "Default")
      (node (ref "U$1") (pin "P9.10") (pinfunction "SYS_RESET~{N}_P9.10") (pintype "bidirectional"))
    )
    (net (code "178") (name "unconnected-(U$1B-VDD_3V3-PadP9.3)") (class "Default")
      (node (ref "U$1") (pin "P9.3") (pinfunction "VDD_3V3_P9.3") (pintype "bidirectional"))
    )
    (net (code "179") (name "unconnected-(U$1B-VDD_3V3-PadP9.4)") (class "Default")
      (node (ref "U$1") (pin "P9.4") (pinfunction "VDD_3V3_P9.4") (pintype "bidirectional"))
    )
    (net (code "180") (name "unconnected-(U$1B-VDD_5V-PadP9.5)") (class "Default")
      (node (ref "U$1") (pin "P9.5") (pinfunction "VDD_5V_P9.5") (pintype "bidirectional"))
    )
    (net (code "181") (name "unconnected-(U$1B-VDD_5V-PadP9.6)") (class "Default")
      (node (ref "U$1") (pin "P9.6") (pinfunction "VDD_5V_P9.6") (pintype "bidirectional"))
    )
    (net (code "182") (name "unconnected-(U$1B-VDD_ADC-PadP9.32)") (class "Default")
      (node (ref "U$1") (pin "P9.32") (pinfunction "VDD_ADC_P9.32") (pintype "bidirectional"))
    )
    (net (code "183") (name "unconnected-(U3-OUT-Pad2)") (class "Default")
      (node (ref "U3") (pin "2") (pinfunction "OUT_2") (pintype "output"))
    )
  )
)
